# MSUT.net
KiCad netlist of a schematic drawn in EAGLE
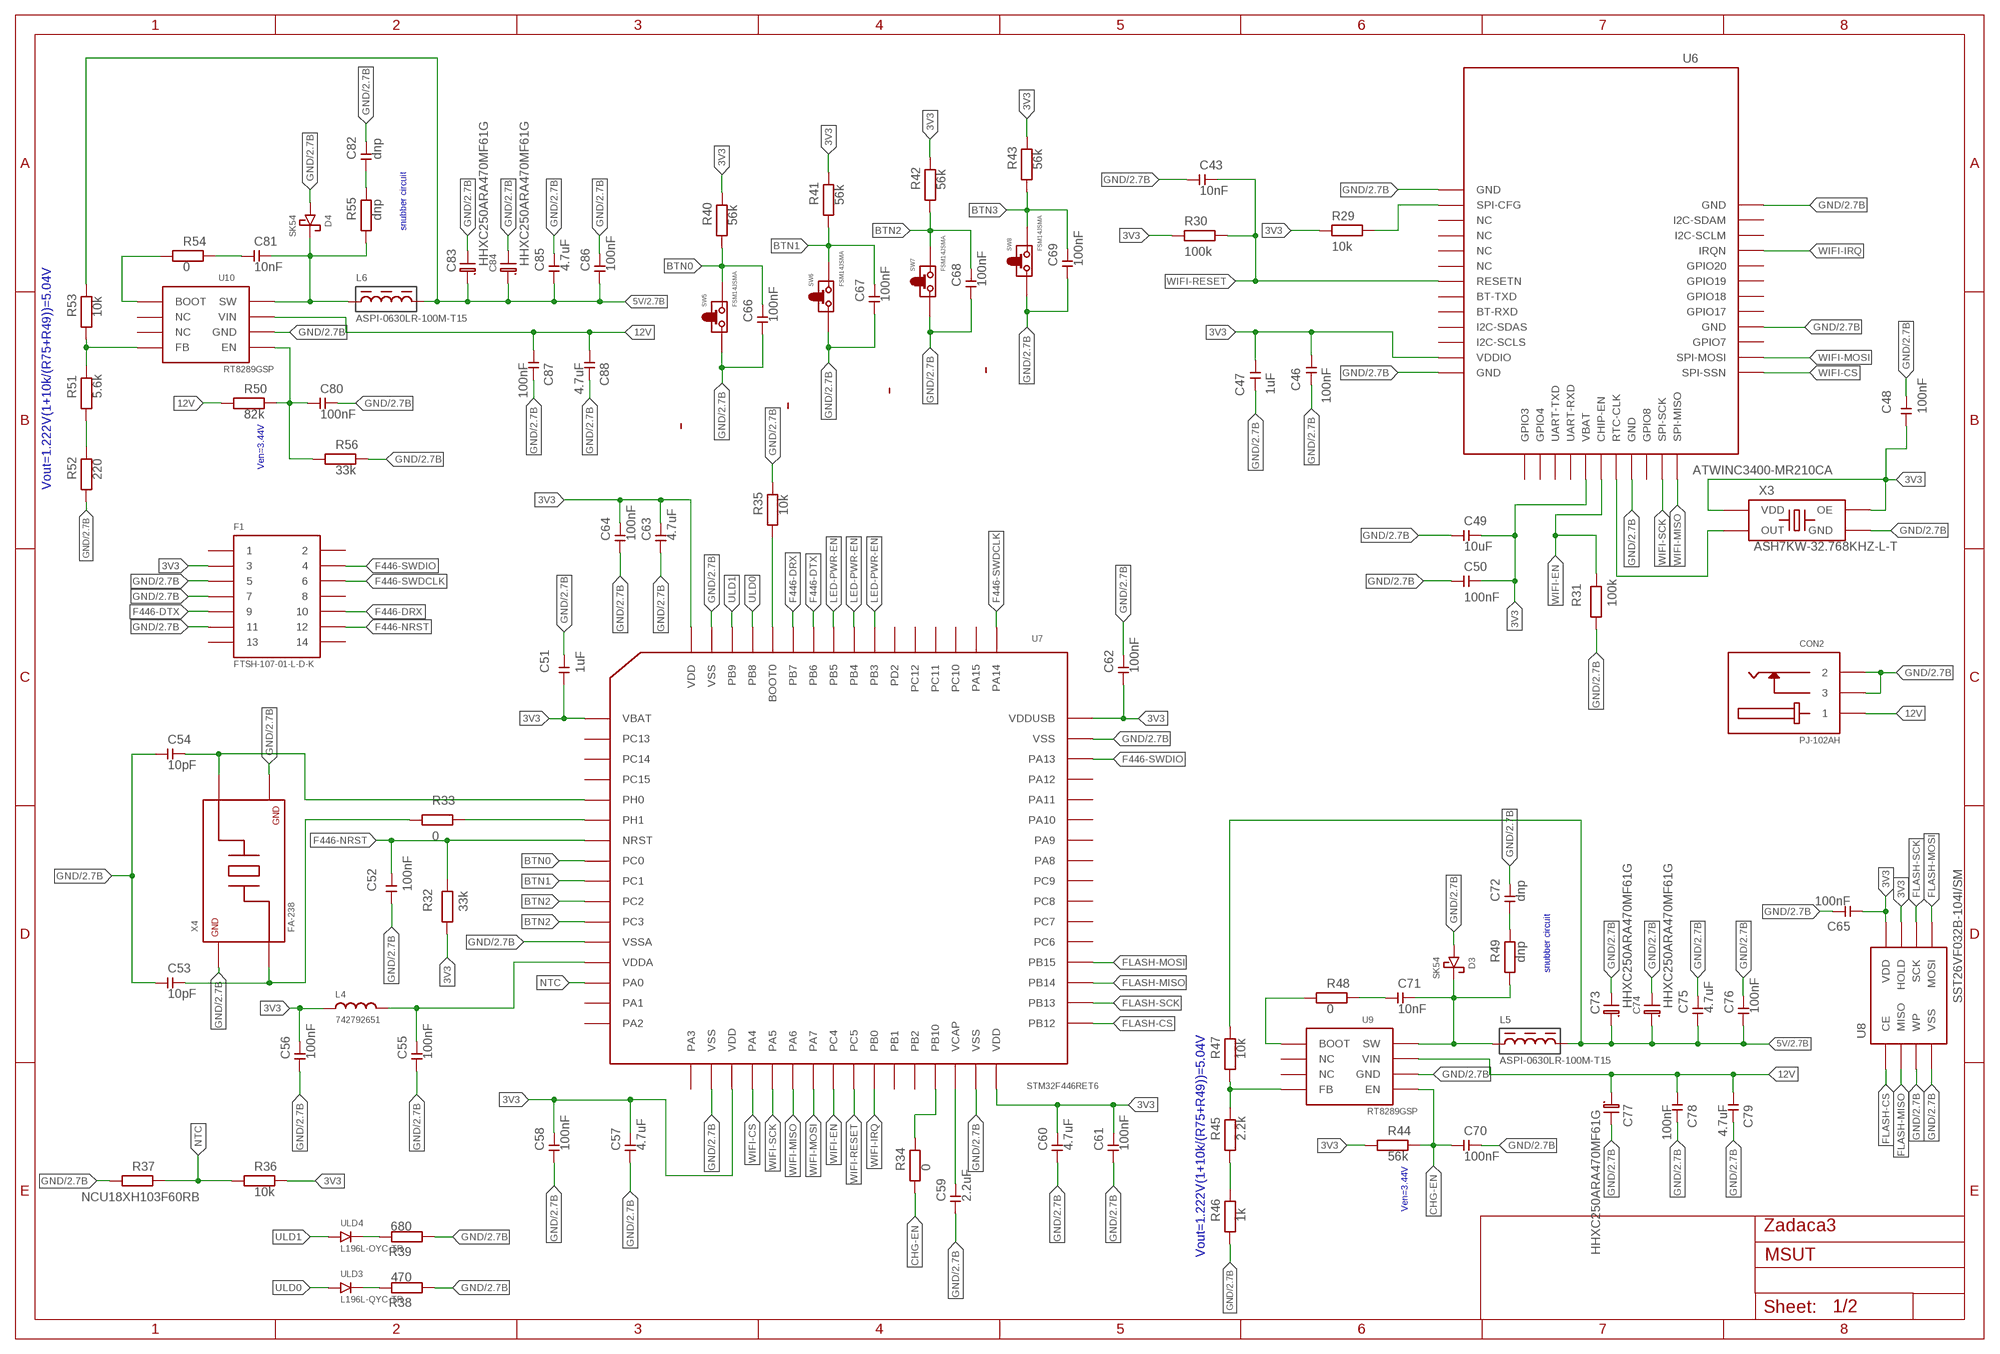
[diagram p0: schematic, sheet 1]
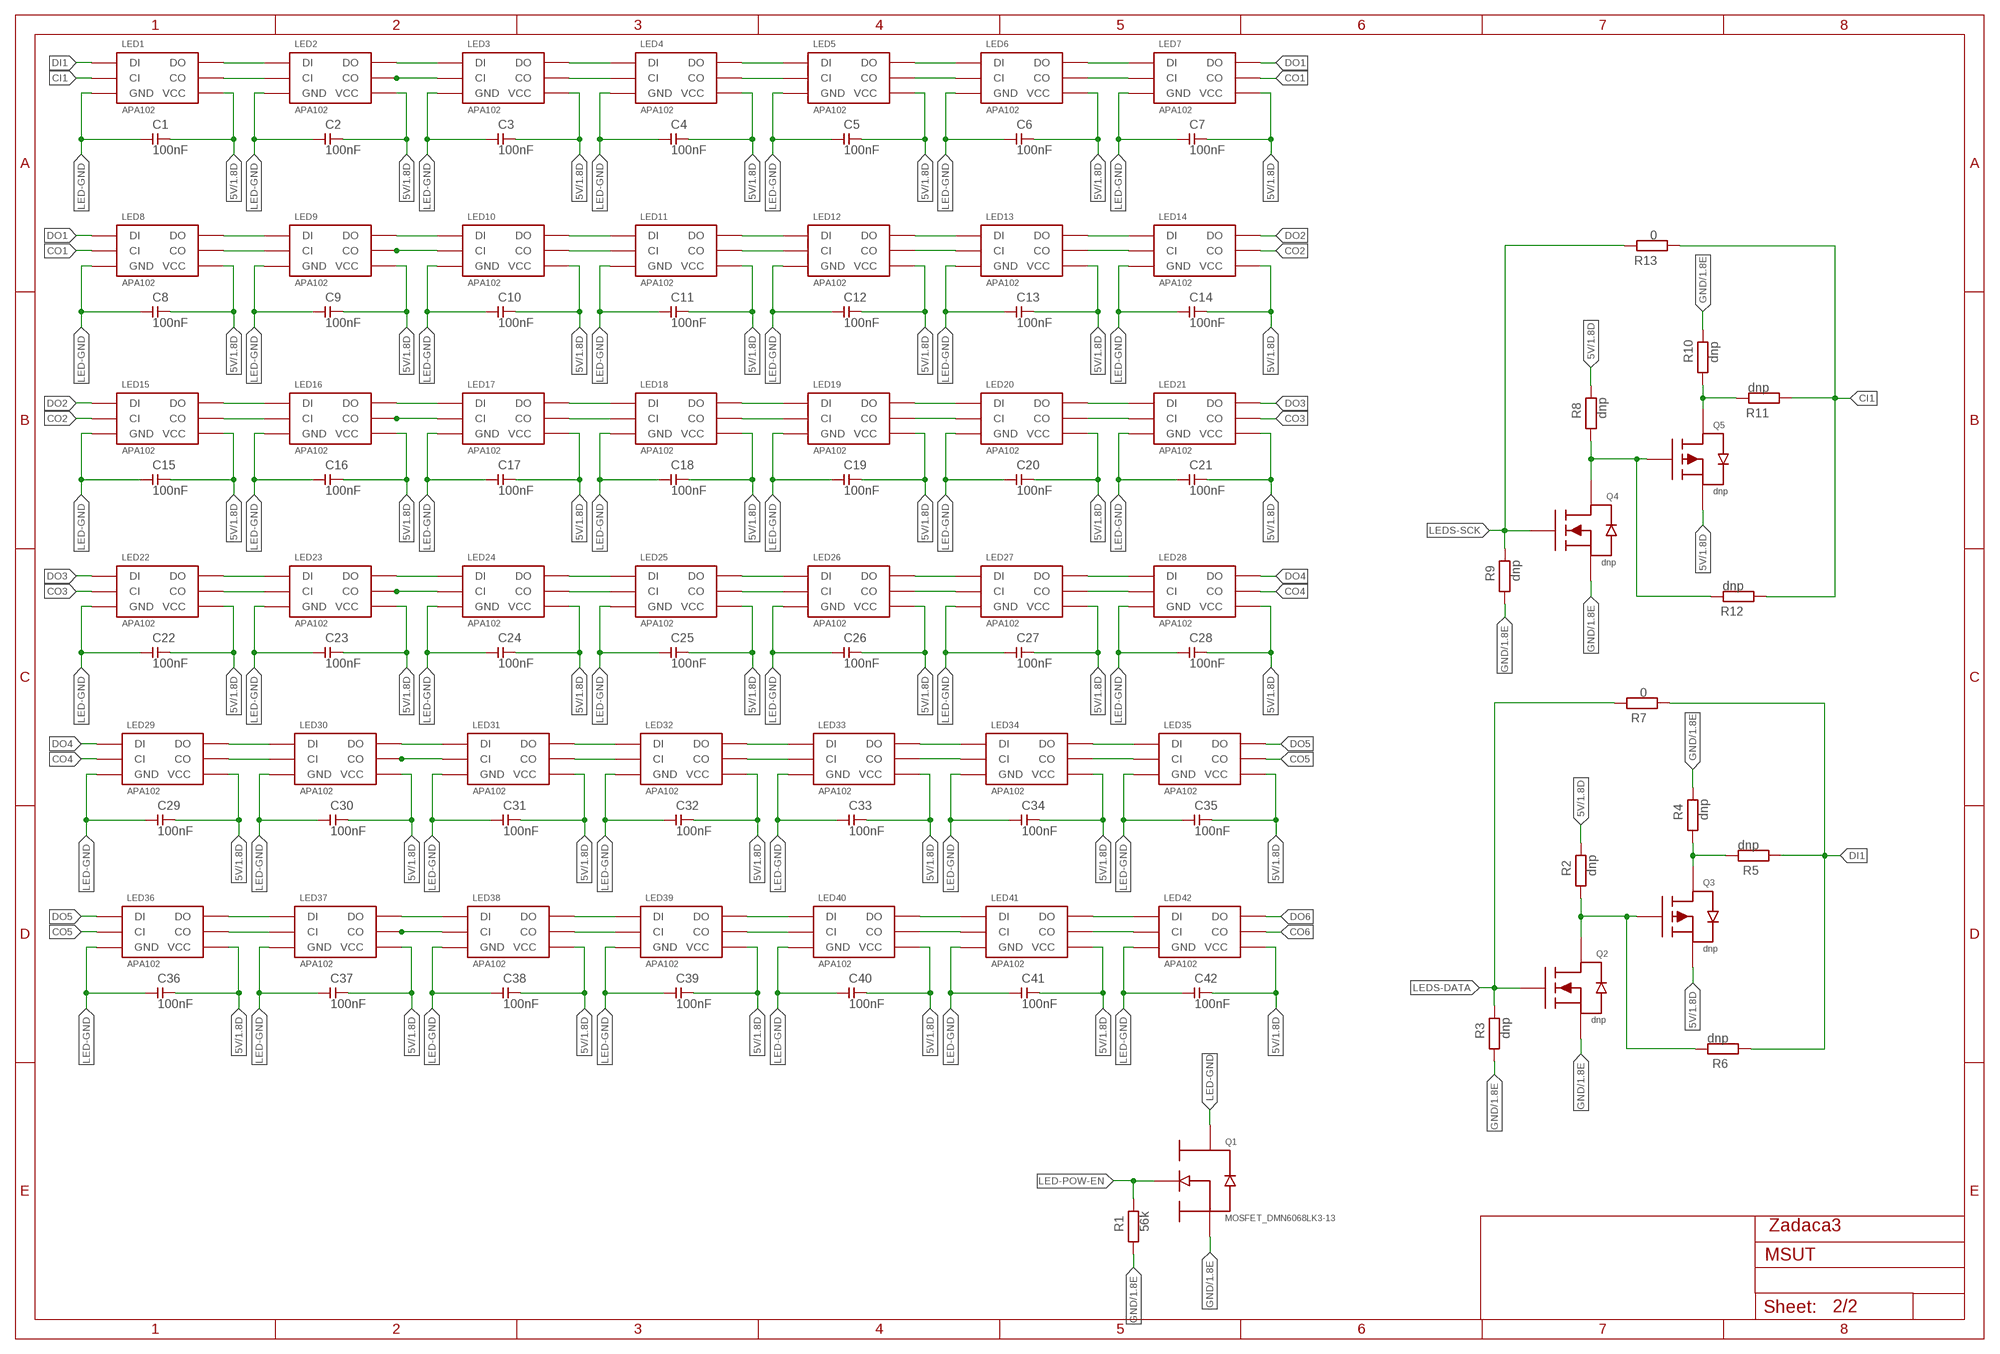
[diagram p1: schematic, sheet 2]

(export (version "E")
  (design (tool "Eeschema 10.0.6"))
  (components
    (comp (ref "C1")
      (value "100nF")
      (footprint "eagle-import:PACKAGE_0805")
      (libsource (lib "eagle-import") (part "CAPACITORB"))
    )
    (comp (ref "C2")
      (value "100nF")
      (footprint "eagle-import:PACKAGE_0805")
      (libsource (lib "eagle-import") (part "CAPACITORB"))
    )
    (comp (ref "C3")
      (value "100nF")
      (footprint "eagle-import:PACKAGE_0805")
      (libsource (lib "eagle-import") (part "CAPACITORB"))
    )
    (comp (ref "C4")
      (value "100nF")
      (footprint "eagle-import:PACKAGE_0805")
      (libsource (lib "eagle-import") (part "CAPACITORB"))
    )
    (comp (ref "C5")
      (value "100nF")
      (footprint "eagle-import:PACKAGE_0805")
      (libsource (lib "eagle-import") (part "CAPACITORB"))
    )
    (comp (ref "C6")
      (value "100nF")
      (footprint "eagle-import:PACKAGE_0805")
      (libsource (lib "eagle-import") (part "CAPACITORB"))
    )
    (comp (ref "C7")
      (value "100nF")
      (footprint "eagle-import:PACKAGE_0805")
      (libsource (lib "eagle-import") (part "CAPACITORB"))
    )
    (comp (ref "C8")
      (value "100nF")
      (footprint "eagle-import:PACKAGE_0805")
      (libsource (lib "eagle-import") (part "CAPACITORB"))
    )
    (comp (ref "C9")
      (value "100nF")
      (footprint "eagle-import:PACKAGE_0805")
      (libsource (lib "eagle-import") (part "CAPACITORB"))
    )
    (comp (ref "C10")
      (value "100nF")
      (footprint "eagle-import:PACKAGE_0805")
      (libsource (lib "eagle-import") (part "CAPACITORB"))
    )
    (comp (ref "C11")
      (value "100nF")
      (footprint "eagle-import:PACKAGE_0805")
      (libsource (lib "eagle-import") (part "CAPACITORB"))
    )
    (comp (ref "C12")
      (value "100nF")
      (footprint "eagle-import:PACKAGE_0805")
      (libsource (lib "eagle-import") (part "CAPACITORB"))
    )
    (comp (ref "C13")
      (value "100nF")
      (footprint "eagle-import:PACKAGE_0805")
      (libsource (lib "eagle-import") (part "CAPACITORB"))
    )
    (comp (ref "C14")
      (value "100nF")
      (footprint "eagle-import:PACKAGE_0805")
      (libsource (lib "eagle-import") (part "CAPACITORB"))
    )
    (comp (ref "C15")
      (value "100nF")
      (footprint "eagle-import:PACKAGE_0805")
      (libsource (lib "eagle-import") (part "CAPACITORB"))
    )
    (comp (ref "C16")
      (value "100nF")
      (footprint "eagle-import:PACKAGE_0805")
      (libsource (lib "eagle-import") (part "CAPACITORB"))
    )
    (comp (ref "C17")
      (value "100nF")
      (footprint "eagle-import:PACKAGE_0805")
      (libsource (lib "eagle-import") (part "CAPACITORB"))
    )
    (comp (ref "C18")
      (value "100nF")
      (footprint "eagle-import:PACKAGE_0805")
      (libsource (lib "eagle-import") (part "CAPACITORB"))
    )
    (comp (ref "C19")
      (value "100nF")
      (footprint "eagle-import:PACKAGE_0805")
      (libsource (lib "eagle-import") (part "CAPACITORB"))
    )
    (comp (ref "C20")
      (value "100nF")
      (footprint "eagle-import:PACKAGE_0805")
      (libsource (lib "eagle-import") (part "CAPACITORB"))
    )
    (comp (ref "C21")
      (value "100nF")
      (footprint "eagle-import:PACKAGE_0805")
      (libsource (lib "eagle-import") (part "CAPACITORB"))
    )
    (comp (ref "C22")
      (value "100nF")
      (footprint "eagle-import:PACKAGE_0805")
      (libsource (lib "eagle-import") (part "CAPACITORB"))
    )
    (comp (ref "C23")
      (value "100nF")
      (footprint "eagle-import:PACKAGE_0805")
      (libsource (lib "eagle-import") (part "CAPACITORB"))
    )
    (comp (ref "C24")
      (value "100nF")
      (footprint "eagle-import:PACKAGE_0805")
      (libsource (lib "eagle-import") (part "CAPACITORB"))
    )
    (comp (ref "C25")
      (value "100nF")
      (footprint "eagle-import:PACKAGE_0805")
      (libsource (lib "eagle-import") (part "CAPACITORB"))
    )
    (comp (ref "C26")
      (value "100nF")
      (footprint "eagle-import:PACKAGE_0805")
      (libsource (lib "eagle-import") (part "CAPACITORB"))
    )
    (comp (ref "C27")
      (value "100nF")
      (footprint "eagle-import:PACKAGE_0805")
      (libsource (lib "eagle-import") (part "CAPACITORB"))
    )
    (comp (ref "C28")
      (value "100nF")
      (footprint "eagle-import:PACKAGE_0805")
      (libsource (lib "eagle-import") (part "CAPACITORB"))
    )
    (comp (ref "C29")
      (value "100nF")
      (footprint "eagle-import:PACKAGE_0805")
      (libsource (lib "eagle-import") (part "CAPACITORB"))
    )
    (comp (ref "C30")
      (value "100nF")
      (footprint "eagle-import:PACKAGE_0805")
      (libsource (lib "eagle-import") (part "CAPACITORB"))
    )
    (comp (ref "C31")
      (value "100nF")
      (footprint "eagle-import:PACKAGE_0805")
      (libsource (lib "eagle-import") (part "CAPACITORB"))
    )
    (comp (ref "C32")
      (value "100nF")
      (footprint "eagle-import:PACKAGE_0805")
      (libsource (lib "eagle-import") (part "CAPACITORB"))
    )
    (comp (ref "C33")
      (value "100nF")
      (footprint "eagle-import:PACKAGE_0805")
      (libsource (lib "eagle-import") (part "CAPACITORB"))
    )
    (comp (ref "C34")
      (value "100nF")
      (footprint "eagle-import:PACKAGE_0805")
      (libsource (lib "eagle-import") (part "CAPACITORB"))
    )
    (comp (ref "C35")
      (value "100nF")
      (footprint "eagle-import:PACKAGE_0805")
      (libsource (lib "eagle-import") (part "CAPACITORB"))
    )
    (comp (ref "C36")
      (value "100nF")
      (footprint "eagle-import:PACKAGE_0805")
      (libsource (lib "eagle-import") (part "CAPACITORB"))
    )
    (comp (ref "C37")
      (value "100nF")
      (footprint "eagle-import:PACKAGE_0805")
      (libsource (lib "eagle-import") (part "CAPACITORB"))
    )
    (comp (ref "C38")
      (value "100nF")
      (footprint "eagle-import:PACKAGE_0805")
      (libsource (lib "eagle-import") (part "CAPACITORB"))
    )
    (comp (ref "C39")
      (value "100nF")
      (footprint "eagle-import:PACKAGE_0805")
      (libsource (lib "eagle-import") (part "CAPACITORB"))
    )
    (comp (ref "C40")
      (value "100nF")
      (footprint "eagle-import:PACKAGE_0805")
      (libsource (lib "eagle-import") (part "CAPACITORB"))
    )
    (comp (ref "C41")
      (value "100nF")
      (footprint "eagle-import:PACKAGE_0805")
      (libsource (lib "eagle-import") (part "CAPACITORB"))
    )
    (comp (ref "C42")
      (value "100nF")
      (footprint "eagle-import:PACKAGE_0805")
      (libsource (lib "eagle-import") (part "CAPACITORB"))
    )
    (comp (ref "LED1")
      (value "RGB_LED")
      (footprint "eagle-import:TAPE&REEL_LED")
      (libsource (lib "eagle-import") (part "RGB_LED"))
    )
    (comp (ref "LED2")
      (value "RGB_LED")
      (footprint "eagle-import:TAPE&REEL_LED")
      (libsource (lib "eagle-import") (part "RGB_LED"))
    )
    (comp (ref "LED3")
      (value "RGB_LED")
      (footprint "eagle-import:TAPE&REEL_LED")
      (libsource (lib "eagle-import") (part "RGB_LED"))
    )
    (comp (ref "LED4")
      (value "RGB_LED")
      (footprint "eagle-import:TAPE&REEL_LED")
      (libsource (lib "eagle-import") (part "RGB_LED"))
    )
    (comp (ref "LED5")
      (value "RGB_LED")
      (footprint "eagle-import:TAPE&REEL_LED")
      (libsource (lib "eagle-import") (part "RGB_LED"))
    )
    (comp (ref "LED6")
      (value "RGB_LED")
      (footprint "eagle-import:TAPE&REEL_LED")
      (libsource (lib "eagle-import") (part "RGB_LED"))
    )
    (comp (ref "LED7")
      (value "RGB_LED")
      (footprint "eagle-import:TAPE&REEL_LED")
      (libsource (lib "eagle-import") (part "RGB_LED"))
    )
    (comp (ref "LED8")
      (value "RGB_LED")
      (footprint "eagle-import:TAPE&REEL_LED")
      (libsource (lib "eagle-import") (part "RGB_LED"))
    )
    (comp (ref "LED9")
      (value "RGB_LED")
      (footprint "eagle-import:TAPE&REEL_LED")
      (libsource (lib "eagle-import") (part "RGB_LED"))
    )
    (comp (ref "LED10")
      (value "RGB_LED")
      (footprint "eagle-import:TAPE&REEL_LED")
      (libsource (lib "eagle-import") (part "RGB_LED"))
    )
    (comp (ref "LED11")
      (value "RGB_LED")
      (footprint "eagle-import:TAPE&REEL_LED")
      (libsource (lib "eagle-import") (part "RGB_LED"))
    )
    (comp (ref "LED12")
      (value "RGB_LED")
      (footprint "eagle-import:TAPE&REEL_LED")
      (libsource (lib "eagle-import") (part "RGB_LED"))
    )
    (comp (ref "LED13")
      (value "RGB_LED")
      (footprint "eagle-import:TAPE&REEL_LED")
      (libsource (lib "eagle-import") (part "RGB_LED"))
    )
    (comp (ref "LED14")
      (value "RGB_LED")
      (footprint "eagle-import:TAPE&REEL_LED")
      (libsource (lib "eagle-import") (part "RGB_LED"))
    )
    (comp (ref "LED15")
      (value "RGB_LED")
      (footprint "eagle-import:TAPE&REEL_LED")
      (libsource (lib "eagle-import") (part "RGB_LED"))
    )
    (comp (ref "LED16")
      (value "RGB_LED")
      (footprint "eagle-import:TAPE&REEL_LED")
      (libsource (lib "eagle-import") (part "RGB_LED"))
    )
    (comp (ref "LED17")
      (value "RGB_LED")
      (footprint "eagle-import:TAPE&REEL_LED")
      (libsource (lib "eagle-import") (part "RGB_LED"))
    )
    (comp (ref "LED18")
      (value "RGB_LED")
      (footprint "eagle-import:TAPE&REEL_LED")
      (libsource (lib "eagle-import") (part "RGB_LED"))
    )
    (comp (ref "LED19")
      (value "RGB_LED")
      (footprint "eagle-import:TAPE&REEL_LED")
      (libsource (lib "eagle-import") (part "RGB_LED"))
    )
    (comp (ref "LED20")
      (value "RGB_LED")
      (footprint "eagle-import:TAPE&REEL_LED")
      (libsource (lib "eagle-import") (part "RGB_LED"))
    )
    (comp (ref "LED21")
      (value "RGB_LED")
      (footprint "eagle-import:TAPE&REEL_LED")
      (libsource (lib "eagle-import") (part "RGB_LED"))
    )
    (comp (ref "LED22")
      (value "RGB_LED")
      (footprint "eagle-import:TAPE&REEL_LED")
      (libsource (lib "eagle-import") (part "RGB_LED"))
    )
    (comp (ref "LED23")
      (value "RGB_LED")
      (footprint "eagle-import:TAPE&REEL_LED")
      (libsource (lib "eagle-import") (part "RGB_LED"))
    )
    (comp (ref "LED24")
      (value "RGB_LED")
      (footprint "eagle-import:TAPE&REEL_LED")
      (libsource (lib "eagle-import") (part "RGB_LED"))
    )
    (comp (ref "LED25")
      (value "RGB_LED")
      (footprint "eagle-import:TAPE&REEL_LED")
      (libsource (lib "eagle-import") (part "RGB_LED"))
    )
    (comp (ref "LED26")
      (value "RGB_LED")
      (footprint "eagle-import:TAPE&REEL_LED")
      (libsource (lib "eagle-import") (part "RGB_LED"))
    )
    (comp (ref "LED27")
      (value "RGB_LED")
      (footprint "eagle-import:TAPE&REEL_LED")
      (libsource (lib "eagle-import") (part "RGB_LED"))
    )
    (comp (ref "LED28")
      (value "RGB_LED")
      (footprint "eagle-import:TAPE&REEL_LED")
      (libsource (lib "eagle-import") (part "RGB_LED"))
    )
    (comp (ref "LED29")
      (value "RGB_LED")
      (footprint "eagle-import:TAPE&REEL_LED")
      (libsource (lib "eagle-import") (part "RGB_LED"))
    )
    (comp (ref "LED30")
      (value "RGB_LED")
      (footprint "eagle-import:TAPE&REEL_LED")
      (libsource (lib "eagle-import") (part "RGB_LED"))
    )
    (comp (ref "LED31")
      (value "RGB_LED")
      (footprint "eagle-import:TAPE&REEL_LED")
      (libsource (lib "eagle-import") (part "RGB_LED"))
    )
    (comp (ref "LED32")
      (value "RGB_LED")
      (footprint "eagle-import:TAPE&REEL_LED")
      (libsource (lib "eagle-import") (part "RGB_LED"))
    )
    (comp (ref "LED33")
      (value "RGB_LED")
      (footprint "eagle-import:TAPE&REEL_LED")
      (libsource (lib "eagle-import") (part "RGB_LED"))
    )
    (comp (ref "LED34")
      (value "RGB_LED")
      (footprint "eagle-import:TAPE&REEL_LED")
      (libsource (lib "eagle-import") (part "RGB_LED"))
    )
    (comp (ref "LED35")
      (value "RGB_LED")
      (footprint "eagle-import:TAPE&REEL_LED")
      (libsource (lib "eagle-import") (part "RGB_LED"))
    )
    (comp (ref "LED36")
      (value "RGB_LED")
      (footprint "eagle-import:TAPE&REEL_LED")
      (libsource (lib "eagle-import") (part "RGB_LED"))
    )
    (comp (ref "LED37")
      (value "RGB_LED")
      (footprint "eagle-import:TAPE&REEL_LED")
      (libsource (lib "eagle-import") (part "RGB_LED"))
    )
    (comp (ref "LED38")
      (value "RGB_LED")
      (footprint "eagle-import:TAPE&REEL_LED")
      (libsource (lib "eagle-import") (part "RGB_LED"))
    )
    (comp (ref "LED39")
      (value "RGB_LED")
      (footprint "eagle-import:TAPE&REEL_LED")
      (libsource (lib "eagle-import") (part "RGB_LED"))
    )
    (comp (ref "LED40")
      (value "RGB_LED")
      (footprint "eagle-import:TAPE&REEL_LED")
      (libsource (lib "eagle-import") (part "RGB_LED"))
    )
    (comp (ref "LED41")
      (value "RGB_LED")
      (footprint "eagle-import:TAPE&REEL_LED")
      (libsource (lib "eagle-import") (part "RGB_LED"))
    )
    (comp (ref "LED42")
      (value "RGB_LED")
      (footprint "eagle-import:TAPE&REEL_LED")
      (libsource (lib "eagle-import") (part "RGB_LED"))
    )
    (comp (ref "Q1")
      (value "MOSFET_DMN6068LK3-13")
      (footprint "eagle-import:TO252-3L")
      (libsource (lib "eagle-import") (part "MOSFET_DMN6068LK3-13"))
    )
    (comp (ref "Q2")
      (value "NCHANNEL_MOSFET")
      (footprint "eagle-import:SOT-23-3")
      (libsource (lib "eagle-import") (part "NCHANNEL_MOSFET"))
    )
    (comp (ref "Q3")
      (value "PCHANNEL_MOSFET")
      (footprint "eagle-import:SOT-23-3")
      (libsource (lib "eagle-import") (part "PCHANNEL_MOSFET"))
    )
    (comp (ref "Q4")
      (value "NCHANNEL_MOSFET")
      (footprint "eagle-import:SOT-23-3")
      (libsource (lib "eagle-import") (part "NCHANNEL_MOSFET"))
    )
    (comp (ref "Q5")
      (value "PCHANNEL_MOSFET")
      (footprint "eagle-import:SOT-23-3")
      (libsource (lib "eagle-import") (part "PCHANNEL_MOSFET"))
    )
    (comp (ref "R1")
      (value "56k")
      (footprint "eagle-import:PACKAGE_0805")
      (libsource (lib "eagle-import") (part "RESISTOR"))
    )
    (comp (ref "R2")
      (value "dnp")
      (footprint "eagle-import:PACKAGE_0805")
      (libsource (lib "eagle-import") (part "RESISTOR"))
    )
    (comp (ref "R3")
      (value "dnp")
      (footprint "eagle-import:PACKAGE_0805")
      (libsource (lib "eagle-import") (part "RESISTOR"))
    )
    (comp (ref "R4")
      (value "dnp")
      (footprint "eagle-import:PACKAGE_0805")
      (libsource (lib "eagle-import") (part "RESISTOR"))
    )
    (comp (ref "R5")
      (value "dnp")
      (footprint "eagle-import:PACKAGE_0805")
      (libsource (lib "eagle-import") (part "RESISTOR"))
    )
    (comp (ref "R6")
      (value "dnp")
      (footprint "eagle-import:PACKAGE_0805")
      (libsource (lib "eagle-import") (part "RESISTOR"))
    )
    (comp (ref "R7")
      (value "0")
      (footprint "eagle-import:PACKAGE_0805")
      (libsource (lib "eagle-import") (part "RESISTOR"))
    )
    (comp (ref "R8")
      (value "dnp")
      (footprint "eagle-import:PACKAGE_0805")
      (libsource (lib "eagle-import") (part "RESISTOR"))
    )
    (comp (ref "R9")
      (value "dnp")
      (footprint "eagle-import:PACKAGE_0805")
      (libsource (lib "eagle-import") (part "RESISTOR"))
    )
    (comp (ref "R10")
      (value "dnp")
      (footprint "eagle-import:PACKAGE_0805")
      (libsource (lib "eagle-import") (part "RESISTOR"))
    )
    (comp (ref "R11")
      (value "dnp")
      (footprint "eagle-import:PACKAGE_0805")
      (libsource (lib "eagle-import") (part "RESISTOR"))
    )
    (comp (ref "R12")
      (value "dnp")
      (footprint "eagle-import:PACKAGE_0805")
      (libsource (lib "eagle-import") (part "RESISTOR"))
    )
    (comp (ref "R13")
      (value "0")
      (footprint "eagle-import:PACKAGE_0805")
      (libsource (lib "eagle-import") (part "RESISTOR"))
    )
    (comp (ref "C43")
      (value "10nF")
      (footprint "eagle-import:PACKAGE_0805")
      (libsource (lib "eagle-import") (part "CAPACITORB"))
    )
    (comp (ref "C46")
      (value "100nF")
      (footprint "eagle-import:PACKAGE_0805")
      (libsource (lib "eagle-import") (part "CAPACITORB"))
    )
    (comp (ref "C47")
      (value "1uF")
      (footprint "eagle-import:PACKAGE_0805")
      (libsource (lib "eagle-import") (part "CAPACITORB"))
    )
    (comp (ref "C48")
      (value "100nF")
      (footprint "eagle-import:PACKAGE_0805")
      (libsource (lib "eagle-import") (part "CAPACITORB"))
    )
    (comp (ref "C49")
      (value "10uF")
      (footprint "eagle-import:PACKAGE_0805")
      (libsource (lib "eagle-import") (part "CAPACITORB"))
    )
    (comp (ref "C50")
      (value "100nF")
      (footprint "eagle-import:PACKAGE_0805")
      (libsource (lib "eagle-import") (part "CAPACITORB"))
    )
    (comp (ref "C51")
      (value "1uF")
      (footprint "eagle-import:PACKAGE_0805")
      (libsource (lib "eagle-import") (part "CAPACITORB"))
    )
    (comp (ref "C52")
      (value "100nF")
      (footprint "eagle-import:PACKAGE_0805")
      (libsource (lib "eagle-import") (part "CAPACITORB"))
    )
    (comp (ref "C53")
      (value "10pF")
      (footprint "eagle-import:PACKAGE_0805")
      (libsource (lib "eagle-import") (part "CAPACITORB"))
    )
    (comp (ref "C54")
      (value "10pF")
      (footprint "eagle-import:PACKAGE_0805")
      (libsource (lib "eagle-import") (part "CAPACITORB"))
    )
    (comp (ref "C55")
      (value "100nF")
      (footprint "eagle-import:PACKAGE_0805")
      (libsource (lib "eagle-import") (part "CAPACITORB"))
    )
    (comp (ref "C56")
      (value "100nF")
      (footprint "eagle-import:PACKAGE_0805")
      (libsource (lib "eagle-import") (part "CAPACITORB"))
    )
    (comp (ref "C57")
      (value "4.7uF")
      (footprint "eagle-import:PACKAGE_0805")
      (libsource (lib "eagle-import") (part "CAPACITORB"))
    )
    (comp (ref "C58")
      (value "100nF")
      (footprint "eagle-import:PACKAGE_0805")
      (libsource (lib "eagle-import") (part "CAPACITORB"))
    )
    (comp (ref "C59")
      (value "2.2uF")
      (footprint "eagle-import:PACKAGE_0805")
      (libsource (lib "eagle-import") (part "CAPACITORB"))
    )
    (comp (ref "C60")
      (value "4.7uF")
      (footprint "eagle-import:PACKAGE_0805")
      (libsource (lib "eagle-import") (part "CAPACITORB"))
    )
    (comp (ref "C61")
      (value "100nF")
      (footprint "eagle-import:PACKAGE_0805")
      (libsource (lib "eagle-import") (part "CAPACITORB"))
    )
    (comp (ref "C62")
      (value "100nF")
      (footprint "eagle-import:PACKAGE_0805")
      (libsource (lib "eagle-import") (part "CAPACITORB"))
    )
    (comp (ref "C63")
      (value "4.7uF")
      (footprint "eagle-import:PACKAGE_0805")
      (libsource (lib "eagle-import") (part "CAPACITORB"))
    )
    (comp (ref "C64")
      (value "100nF")
      (footprint "eagle-import:PACKAGE_0805")
      (libsource (lib "eagle-import") (part "CAPACITORB"))
    )
    (comp (ref "C65")
      (value "100nF")
      (footprint "eagle-import:PACKAGE_0805")
      (libsource (lib "eagle-import") (part "CAPACITORB"))
    )
    (comp (ref "C66")
      (value "100nF")
      (footprint "eagle-import:PACKAGE_0805")
      (libsource (lib "eagle-import") (part "CAPACITORB"))
    )
    (comp (ref "C67")
      (value "100nF")
      (footprint "eagle-import:PACKAGE_0805")
      (libsource (lib "eagle-import") (part "CAPACITORB"))
    )
    (comp (ref "C68")
      (value "100nF")
      (footprint "eagle-import:PACKAGE_0805")
      (libsource (lib "eagle-import") (part "CAPACITORB"))
    )
    (comp (ref "C69")
      (value "100nF")
      (footprint "eagle-import:PACKAGE_0805")
      (libsource (lib "eagle-import") (part "CAPACITORB"))
    )
    (comp (ref "C70")
      (value "100nF")
      (footprint "eagle-import:PACKAGE_0805")
      (libsource (lib "eagle-import") (part "CAPACITORB"))
    )
    (comp (ref "C71")
      (value "10nF")
      (footprint "eagle-import:PACKAGE_0805")
      (libsource (lib "eagle-import") (part "CAPACITORB"))
    )
    (comp (ref "C72")
      (value "dnp")
      (footprint "eagle-import:PACKAGE_0805")
      (libsource (lib "eagle-import") (part "CAPACITORB"))
    )
    (comp (ref "C73")
      (value "HHXC250ARA470MF61G")
      (footprint "eagle-import:PACKAGE_EL_CAP_HXC")
      (libsource (lib "eagle-import") (part "ELECTROLIC_CAPACTIOR"))
    )
    (comp (ref "C74")
      (value "HHXC250ARA470MF61G")
      (footprint "eagle-import:PACKAGE_EL_CAP_HXC")
      (libsource (lib "eagle-import") (part "ELECTROLIC_CAPACTIOR"))
    )
    (comp (ref "C75")
      (value "4.7uF")
      (footprint "eagle-import:PACKAGE_0805")
      (libsource (lib "eagle-import") (part "CAPACITORB"))
    )
    (comp (ref "C76")
      (value "100nF")
      (footprint "eagle-import:PACKAGE_0805")
      (libsource (lib "eagle-import") (part "CAPACITORB"))
    )
    (comp (ref "C77")
      (value "HHXB350ARA470MF61G")
      (footprint "eagle-import:PACKAGE_EL_CAP_HXC")
      (libsource (lib "eagle-import") (part "ELECTROLIC_CAPACTIOR"))
    )
    (comp (ref "C78")
      (value "100nF")
      (footprint "eagle-import:PACKAGE_0805")
      (libsource (lib "eagle-import") (part "CAPACITORB"))
    )
    (comp (ref "C79")
      (value "4.7uF")
      (footprint "eagle-import:PACKAGE_0805")
      (libsource (lib "eagle-import") (part "CAPACITORB"))
    )
    (comp (ref "C80")
      (value "100nF")
      (footprint "eagle-import:PACKAGE_0805")
      (libsource (lib "eagle-import") (part "CAPACITORB"))
    )
    (comp (ref "C81")
      (value "10nF")
      (footprint "eagle-import:PACKAGE_0805")
      (libsource (lib "eagle-import") (part "CAPACITORB"))
    )
    (comp (ref "C82")
      (value "dnp")
      (footprint "eagle-import:PACKAGE_0805")
      (libsource (lib "eagle-import") (part "CAPACITORB"))
    )
    (comp (ref "C83")
      (value "HHXC250ARA470MF61G")
      (footprint "eagle-import:PACKAGE_EL_CAP_HXC")
      (libsource (lib "eagle-import") (part "ELECTROLIC_CAPACTIOR"))
    )
    (comp (ref "C84")
      (value "HHXC250ARA470MF61G")
      (footprint "eagle-import:PACKAGE_EL_CAP_HXC")
      (libsource (lib "eagle-import") (part "ELECTROLIC_CAPACTIOR"))
    )
    (comp (ref "C85")
      (value "4.7uF")
      (footprint "eagle-import:PACKAGE_0805")
      (libsource (lib "eagle-import") (part "CAPACITORB"))
    )
    (comp (ref "C86")
      (value "100nF")
      (footprint "eagle-import:PACKAGE_0805")
      (libsource (lib "eagle-import") (part "CAPACITORB"))
    )
    (comp (ref "C87")
      (value "100nF")
      (footprint "eagle-import:PACKAGE_0805")
      (libsource (lib "eagle-import") (part "CAPACITORB"))
    )
    (comp (ref "C88")
      (value "4.7uF")
      (footprint "eagle-import:PACKAGE_0805")
      (libsource (lib "eagle-import") (part "CAPACITORB"))
    )
    (comp (ref "CON2")
      (value "PJ-102AH")
      (footprint "eagle-import:TRAY_PJ-102AH")
      (libsource (lib "eagle-import") (part "PJ-102AH_CONNECTOR"))
    )
    (comp (ref "D3")
      (value "SK54")
      (footprint "eagle-import:D0-214AB")
      (libsource (lib "eagle-import") (part "SHOTTKY_DIODE"))
    )
    (comp (ref "D4")
      (value "SK54")
      (footprint "eagle-import:D0-214AB")
      (libsource (lib "eagle-import") (part "SHOTTKY_DIODE"))
    )
    (comp (ref "F1")
      (value "FTSH-107-01-L-D-K")
      (footprint "eagle-import:TUBE_FTSH-107-01-L-D-K")
      (libsource (lib "eagle-import") (part "FTSH-107-01-L-D-K"))
    )
    (comp (ref "L4")
      (value "742792651")
      (footprint "eagle-import:PACKAGE_0805")
      (libsource (lib "eagle-import") (part "INDUCTOR"))
    )
    (comp (ref "L5")
      (value "ASPI-0630LR-100M-T15")
      (footprint "eagle-import:PACKAGE_ASPI-0630")
      (libsource (lib "eagle-import") (part "ASPI-0630LR-100M-T15"))
    )
    (comp (ref "L6")
      (value "ASPI-0630LR-100M-T15")
      (footprint "eagle-import:PACKAGE_ASPI-0630")
      (libsource (lib "eagle-import") (part "ASPI-0630LR-100M-T15"))
    )
    (comp (ref "R29")
      (value "10k")
      (footprint "eagle-import:PACKAGE_0805")
      (libsource (lib "eagle-import") (part "RESISTOR"))
    )
    (comp (ref "R30")
      (value "100k")
      (footprint "eagle-import:PACKAGE_0805")
      (libsource (lib "eagle-import") (part "RESISTOR"))
    )
    (comp (ref "R31")
      (value "100k")
      (footprint "eagle-import:PACKAGE_0805")
      (libsource (lib "eagle-import") (part "RESISTOR"))
    )
    (comp (ref "R32")
      (value "33k")
      (footprint "eagle-import:PACKAGE_0805")
      (libsource (lib "eagle-import") (part "RESISTOR"))
    )
    (comp (ref "R33")
      (value "0")
      (footprint "eagle-import:PACKAGE_0805")
      (libsource (lib "eagle-import") (part "RESISTOR"))
    )
    (comp (ref "R34")
      (value "0")
      (footprint "eagle-import:PACKAGE_0805")
      (libsource (lib "eagle-import") (part "RESISTOR"))
    )
    (comp (ref "R35")
      (value "10k")
      (footprint "eagle-import:PACKAGE_0805")
      (libsource (lib "eagle-import") (part "RESISTOR"))
    )
    (comp (ref "R36")
      (value "10k")
      (footprint "eagle-import:PACKAGE_0805")
      (libsource (lib "eagle-import") (part "RESISTOR"))
    )
    (comp (ref "R37")
      (value "NCU18XH103F60RB")
      (footprint "eagle-import:PACKAGE_0805")
      (libsource (lib "eagle-import") (part "RESISTOR"))
    )
    (comp (ref "R38")
      (value "470")
      (footprint "eagle-import:PACKAGE_0805")
      (libsource (lib "eagle-import") (part "RESISTOR"))
    )
    (comp (ref "R39")
      (value "680")
      (footprint "eagle-import:PACKAGE_0805")
      (libsource (lib "eagle-import") (part "RESISTOR"))
    )
    (comp (ref "R40")
      (value "56k")
      (footprint "eagle-import:PACKAGE_0805")
      (libsource (lib "eagle-import") (part "RESISTOR"))
    )
    (comp (ref "R41")
      (value "56k")
      (footprint "eagle-import:PACKAGE_0805")
      (libsource (lib "eagle-import") (part "RESISTOR"))
    )
    (comp (ref "R42")
      (value "56k")
      (footprint "eagle-import:PACKAGE_0805")
      (libsource (lib "eagle-import") (part "RESISTOR"))
    )
    (comp (ref "R43")
      (value "56k")
      (footprint "eagle-import:PACKAGE_0805")
      (libsource (lib "eagle-import") (part "RESISTOR"))
    )
    (comp (ref "R44")
      (value "56k")
      (footprint "eagle-import:PACKAGE_0805")
      (libsource (lib "eagle-import") (part "RESISTOR"))
    )
    (comp (ref "R45")
      (value "2.2k")
      (footprint "eagle-import:PACKAGE_0805")
      (libsource (lib "eagle-import") (part "RESISTOR"))
    )
    (comp (ref "R46")
      (value "1k")
      (footprint "eagle-import:PACKAGE_0805")
      (libsource (lib "eagle-import") (part "RESISTOR"))
    )
    (comp (ref "R47")
      (value "10k")
      (footprint "eagle-import:PACKAGE_0805")
      (libsource (lib "eagle-import") (part "RESISTOR"))
    )
    (comp (ref "R48")
      (value "0")
      (footprint "eagle-import:PACKAGE_0805")
      (libsource (lib "eagle-import") (part "RESISTOR"))
    )
    (comp (ref "R49")
      (value "dnp")
      (footprint "eagle-import:PACKAGE_0805")
      (libsource (lib "eagle-import") (part "RESISTOR"))
    )
    (comp (ref "R50")
      (value "82k")
      (footprint "eagle-import:PACKAGE_0805")
      (libsource (lib "eagle-import") (part "RESISTOR"))
    )
    (comp (ref "R51")
      (value "5.6k")
      (footprint "eagle-import:PACKAGE_0805")
      (libsource (lib "eagle-import") (part "RESISTOR"))
    )
    (comp (ref "R52")
      (value "220")
      (footprint "eagle-import:PACKAGE_0805")
      (libsource (lib "eagle-import") (part "RESISTOR"))
    )
    (comp (ref "R53")
      (value "10k")
      (footprint "eagle-import:PACKAGE_0805")
      (libsource (lib "eagle-import") (part "RESISTOR"))
    )
    (comp (ref "R54")
      (value "0")
      (footprint "eagle-import:PACKAGE_0805")
      (libsource (lib "eagle-import") (part "RESISTOR"))
    )
    (comp (ref "R55")
      (value "dnp")
      (footprint "eagle-import:PACKAGE_0805")
      (libsource (lib "eagle-import") (part "RESISTOR"))
    )
    (comp (ref "R56")
      (value "33k")
      (footprint "eagle-import:PACKAGE_0805")
      (libsource (lib "eagle-import") (part "RESISTOR"))
    )
    (comp (ref "SW5")
      (value "FSM14JSMA")
      (footprint "eagle-import:FSM14JSMA")
      (libsource (lib "eagle-import") (part "PUSHBUTTON"))
    )
    (comp (ref "SW6")
      (value "FSM14JSMA")
      (footprint "eagle-import:FSM14JSMA")
      (libsource (lib "eagle-import") (part "PUSHBUTTON"))
    )
    (comp (ref "SW7")
      (value "FSM14JSMA")
      (footprint "eagle-import:FSM14JSMA")
      (libsource (lib "eagle-import") (part "PUSHBUTTON"))
    )
    (comp (ref "SW8")
      (value "FSM14JSMA")
      (footprint "eagle-import:FSM14JSMA")
      (libsource (lib "eagle-import") (part "PUSHBUTTON"))
    )
    (comp (ref "U6")
      (value "NETWORK_CONTROLLER")
      (footprint "eagle-import:PACKAGE_ATWINC3400-MR210XA")
      (libsource (lib "eagle-import") (part "NETWORK_CONTROLLER"))
    )
    (comp (ref "U7")
      (value "STM32F446RET6")
      (footprint "eagle-import:TRAY_STM32F446RET6")
      (libsource (lib "eagle-import") (part "STM32F446RET6"))
    )
    (comp (ref "U8")
      (value "SST26VF032B-104I/SM")
      (footprint "eagle-import:8-SOIJ")
      (libsource (lib "eagle-import") (part "SST26VF032B-104I/SM"))
    )
    (comp (ref "U9")
      (value "RT8289GSP")
      (footprint "eagle-import:8-SOIC")
      (libsource (lib "eagle-import") (part "RT8289GSP"))
    )
    (comp (ref "U10")
      (value "RT8289GSP")
      (footprint "eagle-import:8-SOIC")
      (libsource (lib "eagle-import") (part "RT8289GSP"))
    )
    (comp (ref "ULD3")
      (value "L196L-QYC-TR")
      (footprint "eagle-import:TAPE&REEL_DIODE")
      (libsource (lib "eagle-import") (part "LED"))
    )
    (comp (ref "ULD4")
      (value "L196L-OYC-TR")
      (footprint "eagle-import:TAPE&REEL_DIODE")
      (libsource (lib "eagle-import") (part "LED"))
    )
    (comp (ref "X3")
      (value "ASH7KW-32.768KHZ-L-T")
      (footprint "eagle-import:PACKAGE_ASH7KW")
      (libsource (lib "eagle-import") (part "ASH7KW-32.768KHZ-L-T"))
    )
    (comp (ref "X4")
      (value "FA-238")
      (footprint "eagle-import:PACKAGE_FA-23816.0000MB-K0")
      (libsource (lib "eagle-import") (part "FA-238"))
    )
  )
  (nets
    (net (code "1") (name "3V3") (class "Default")
      (node (ref "C46") (pin "P1") (pinfunction "P1_P1") (pintype "bidirectional"))
      (node (ref "C47") (pin "P1") (pinfunction "P1_P1") (pintype "bidirectional"))
      (node (ref "C48") (pin "P1") (pinfunction "P1_P1") (pintype "bidirectional"))
      (node (ref "C49") (pin "P2") (pinfunction "P2_P2") (pintype "bidirectional"))
      (node (ref "C50") (pin "P2") (pinfunction "P2_P2") (pintype "bidirectional"))
      (node (ref "C51") (pin "P1") (pinfunction "P1_P1") (pintype "bidirectional"))
      (node (ref "C56") (pin "P2") (pinfunction "P2_P2") (pintype "bidirectional"))
      (node (ref "C57") (pin "P2") (pinfunction "P2_P2") (pintype "bidirectional"))
      (node (ref "C58") (pin "P2") (pinfunction "P2_P2") (pintype "bidirectional"))
      (node (ref "C60") (pin "P2") (pinfunction "P2_P2") (pintype "bidirectional"))
      (node (ref "C61") (pin "P2") (pinfunction "P2_P2") (pintype "bidirectional"))
      (node (ref "C62") (pin "P1") (pinfunction "P1_P1") (pintype "bidirectional"))
      (node (ref "C63") (pin "P2") (pinfunction "P2_P2") (pintype "bidirectional"))
      (node (ref "C64") (pin "P2") (pinfunction "P2_P2") (pintype "bidirectional"))
      (node (ref "C65") (pin "P1") (pinfunction "P1_P1") (pintype "bidirectional"))
      (node (ref "F1") (pin "3") (pinfunction "3_3") (pintype "bidirectional"))
      (node (ref "L4") (pin "P1") (pinfunction "PIN1_P1") (pintype "bidirectional"))
      (node (ref "R29") (pin "P1") (pinfunction "P1_P1") (pintype "bidirectional"))
      (node (ref "R30") (pin "P1") (pinfunction "P1_P1") (pintype "bidirectional"))
      (node (ref "R32") (pin "P1") (pinfunction "P1_P1") (pintype "bidirectional"))
      (node (ref "R36") (pin "P2") (pinfunction "P2_P2") (pintype "bidirectional"))
      (node (ref "R40") (pin "P2") (pinfunction "P2_P2") (pintype "bidirectional"))
      (node (ref "R41") (pin "P2") (pinfunction "P2_P2") (pintype "bidirectional"))
      (node (ref "R42") (pin "P2") (pinfunction "P2_P2") (pintype "bidirectional"))
      (node (ref "R43") (pin "P2") (pinfunction "P2_P2") (pintype "bidirectional"))
      (node (ref "R44") (pin "P1") (pinfunction "P1_P1") (pintype "bidirectional"))
      (node (ref "U6") (pin "VBAT") (pinfunction "VBAT_VBAT") (pintype "bidirectional"))
      (node (ref "U6") (pin "VDDIO") (pinfunction "VDDIO_VDDIO") (pintype "bidirectional"))
      (node (ref "U7") (pin "VBAT") (pinfunction "VBAT_VBAT") (pintype "bidirectional"))
      (node (ref "U7") (pin "VDD1") (pinfunction "VDD_VDD1") (pintype "bidirectional"))
      (node (ref "U7") (pin "VDD2") (pinfunction "VDD_VDD2") (pintype "bidirectional"))
      (node (ref "U7") (pin "VDD3") (pinfunction "VDD_VDD3") (pintype "bidirectional"))
      (node (ref "U7") (pin "VDDUSB") (pinfunction "VDDUSB_VDDUSB") (pintype "bidirectional"))
      (node (ref "U8") (pin "HOLD") (pinfunction "HOLD_HOLD") (pintype "bidirectional"))
      (node (ref "U8") (pin "VDD") (pinfunction "VDD_VDD") (pintype "bidirectional"))
      (node (ref "X3") (pin "OE") (pinfunction "OE_OE") (pintype "bidirectional"))
      (node (ref "X3") (pin "VDD") (pinfunction "VDD_VDD") (pintype "bidirectional"))
    )
    (net (code "2") (name "5V") (class "Default")
      (node (ref "C1") (pin "P2") (pinfunction "P2_P2") (pintype "bidirectional"))
      (node (ref "C10") (pin "P2") (pinfunction "P2_P2") (pintype "bidirectional"))
      (node (ref "C11") (pin "P2") (pinfunction "P2_P2") (pintype "bidirectional"))
      (node (ref "C12") (pin "P2") (pinfunction "P2_P2") (pintype "bidirectional"))
      (node (ref "C13") (pin "P2") (pinfunction "P2_P2") (pintype "bidirectional"))
      (node (ref "C14") (pin "P2") (pinfunction "P2_P2") (pintype "bidirectional"))
      (node (ref "C15") (pin "P2") (pinfunction "P2_P2") (pintype "bidirectional"))
      (node (ref "C16") (pin "P2") (pinfunction "P2_P2") (pintype "bidirectional"))
      (node (ref "C17") (pin "P2") (pinfunction "P2_P2") (pintype "bidirectional"))
      (node (ref "C18") (pin "P2") (pinfunction "P2_P2") (pintype "bidirectional"))
      (node (ref "C19") (pin "P2") (pinfunction "P2_P2") (pintype "bidirectional"))
      (node (ref "C2") (pin "P2") (pinfunction "P2_P2") (pintype "bidirectional"))
      (node (ref "C20") (pin "P2") (pinfunction "P2_P2") (pintype "bidirectional"))
      (node (ref "C21") (pin "P2") (pinfunction "P2_P2") (pintype "bidirectional"))
      (node (ref "C22") (pin "P2") (pinfunction "P2_P2") (pintype "bidirectional"))
      (node (ref "C23") (pin "P2") (pinfunction "P2_P2") (pintype "bidirectional"))
      (node (ref "C24") (pin "P2") (pinfunction "P2_P2") (pintype "bidirectional"))
      (node (ref "C25") (pin "P2") (pinfunction "P2_P2") (pintype "bidirectional"))
      (node (ref "C26") (pin "P2") (pinfunction "P2_P2") (pintype "bidirectional"))
      (node (ref "C27") (pin "P2") (pinfunction "P2_P2") (pintype "bidirectional"))
      (node (ref "C28") (pin "P2") (pinfunction "P2_P2") (pintype "bidirectional"))
      (node (ref "C29") (pin "P2") (pinfunction "P2_P2") (pintype "bidirectional"))
      (node (ref "C3") (pin "P2") (pinfunction "P2_P2") (pintype "bidirectional"))
      (node (ref "C30") (pin "P2") (pinfunction "P2_P2") (pintype "bidirectional"))
      (node (ref "C31") (pin "P2") (pinfunction "P2_P2") (pintype "bidirectional"))
      (node (ref "C32") (pin "P2") (pinfunction "P2_P2") (pintype "bidirectional"))
      (node (ref "C33") (pin "P2") (pinfunction "P2_P2") (pintype "bidirectional"))
      (node (ref "C34") (pin "P2") (pinfunction "P2_P2") (pintype "bidirectional"))
      (node (ref "C35") (pin "P2") (pinfunction "P2_P2") (pintype "bidirectional"))
      (node (ref "C36") (pin "P2") (pinfunction "P2_P2") (pintype "bidirectional"))
      (node (ref "C37") (pin "P2") (pinfunction "P2_P2") (pintype "bidirectional"))
      (node (ref "C38") (pin "P2") (pinfunction "P2_P2") (pintype "bidirectional"))
      (node (ref "C39") (pin "P2") (pinfunction "P2_P2") (pintype "bidirectional"))
      (node (ref "C4") (pin "P2") (pinfunction "P2_P2") (pintype "bidirectional"))
      (node (ref "C40") (pin "P2") (pinfunction "P2_P2") (pintype "bidirectional"))
      (node (ref "C41") (pin "P2") (pinfunction "P2_P2") (pintype "bidirectional"))
      (node (ref "C42") (pin "P2") (pinfunction "P2_P2") (pintype "bidirectional"))
      (node (ref "C5") (pin "P2") (pinfunction "P2_P2") (pintype "bidirectional"))
      (node (ref "C6") (pin "P2") (pinfunction "P2_P2") (pintype "bidirectional"))
      (node (ref "C7") (pin "P2") (pinfunction "P2_P2") (pintype "bidirectional"))
      (node (ref "C73") (pin "P1") (pinfunction "P1_P1") (pintype "bidirectional"))
      (node (ref "C74") (pin "P1") (pinfunction "P1_P1") (pintype "bidirectional"))
      (node (ref "C75") (pin "P1") (pinfunction "P1_P1") (pintype "bidirectional"))
      (node (ref "C76") (pin "P1") (pinfunction "P1_P1") (pintype "bidirectional"))
      (node (ref "C8") (pin "P2") (pinfunction "P2_P2") (pintype "bidirectional"))
      (node (ref "C83") (pin "P1") (pinfunction "P1_P1") (pintype "bidirectional"))
      (node (ref "C84") (pin "P1") (pinfunction "P1_P1") (pintype "bidirectional"))
      (node (ref "C85") (pin "P1") (pinfunction "P1_P1") (pintype "bidirectional"))
      (node (ref "C86") (pin "P1") (pinfunction "P1_P1") (pintype "bidirectional"))
      (node (ref "C9") (pin "P2") (pinfunction "P2_P2") (pintype "bidirectional"))
      (node (ref "L5") (pin "PIN2") (pinfunction "PIN2_PIN2") (pintype "bidirectional"))
      (node (ref "L6") (pin "PIN2") (pinfunction "PIN2_PIN2") (pintype "bidirectional"))
      (node (ref "LED1") (pin "VDD") (pinfunction "VCC_VDD") (pintype "bidirectional"))
      (node (ref "LED10") (pin "VDD") (pinfunction "VCC_VDD") (pintype "bidirectional"))
      (node (ref "LED11") (pin "VDD") (pinfunction "VCC_VDD") (pintype "bidirectional"))
      (node (ref "LED12") (pin "VDD") (pinfunction "VCC_VDD") (pintype "bidirectional"))
      (node (ref "LED13") (pin "VDD") (pinfunction "VCC_VDD") (pintype "bidirectional"))
      (node (ref "LED14") (pin "VDD") (pinfunction "VCC_VDD") (pintype "bidirectional"))
      (node (ref "LED15") (pin "VDD") (pinfunction "VCC_VDD") (pintype "bidirectional"))
      (node (ref "LED16") (pin "VDD") (pinfunction "VCC_VDD") (pintype "bidirectional"))
      (node (ref "LED17") (pin "VDD") (pinfunction "VCC_VDD") (pintype "bidirectional"))
      (node (ref "LED18") (pin "VDD") (pinfunction "VCC_VDD") (pintype "bidirectional"))
      (node (ref "LED19") (pin "VDD") (pinfunction "VCC_VDD") (pintype "bidirectional"))
      (node (ref "LED2") (pin "VDD") (pinfunction "VCC_VDD") (pintype "bidirectional"))
      (node (ref "LED20") (pin "VDD") (pinfunction "VCC_VDD") (pintype "bidirectional"))
      (node (ref "LED21") (pin "VDD") (pinfunction "VCC_VDD") (pintype "bidirectional"))
      (node (ref "LED22") (pin "VDD") (pinfunction "VCC_VDD") (pintype "bidirectional"))
      (node (ref "LED23") (pin "VDD") (pinfunction "VCC_VDD") (pintype "bidirectional"))
      (node (ref "LED24") (pin "VDD") (pinfunction "VCC_VDD") (pintype "bidirectional"))
      (node (ref "LED25") (pin "VDD") (pinfunction "VCC_VDD") (pintype "bidirectional"))
      (node (ref "LED26") (pin "VDD") (pinfunction "VCC_VDD") (pintype "bidirectional"))
      (node (ref "LED27") (pin "VDD") (pinfunction "VCC_VDD") (pintype "bidirectional"))
      (node (ref "LED28") (pin "VDD") (pinfunction "VCC_VDD") (pintype "bidirectional"))
      (node (ref "LED29") (pin "VDD") (pinfunction "VCC_VDD") (pintype "bidirectional"))
      (node (ref "LED3") (pin "VDD") (pinfunction "VCC_VDD") (pintype "bidirectional"))
      (node (ref "LED30") (pin "VDD") (pinfunction "VCC_VDD") (pintype "bidirectional"))
      (node (ref "LED31") (pin "VDD") (pinfunction "VCC_VDD") (pintype "bidirectional"))
      (node (ref "LED32") (pin "VDD") (pinfunction "VCC_VDD") (pintype "bidirectional"))
      (node (ref "LED33") (pin "VDD") (pinfunction "VCC_VDD") (pintype "bidirectional"))
      (node (ref "LED34") (pin "VDD") (pinfunction "VCC_VDD") (pintype "bidirectional"))
      (node (ref "LED35") (pin "VDD") (pinfunction "VCC_VDD") (pintype "bidirectional"))
      (node (ref "LED36") (pin "VDD") (pinfunction "VCC_VDD") (pintype "bidirectional"))
      (node (ref "LED37") (pin "VDD") (pinfunction "VCC_VDD") (pintype "bidirectional"))
      (node (ref "LED38") (pin "VDD") (pinfunction "VCC_VDD") (pintype "bidirectional"))
      (node (ref "LED39") (pin "VDD") (pinfunction "VCC_VDD") (pintype "bidirectional"))
      (node (ref "LED4") (pin "VDD") (pinfunction "VCC_VDD") (pintype "bidirectional"))
      (node (ref "LED40") (pin "VDD") (pinfunction "VCC_VDD") (pintype "bidirectional"))
      (node (ref "LED41") (pin "VDD") (pinfunction "VCC_VDD") (pintype "bidirectional"))
      (node (ref "LED42") (pin "VDD") (pinfunction "VCC_VDD") (pintype "bidirectional"))
      (node (ref "LED5") (pin "VDD") (pinfunction "VCC_VDD") (pintype "bidirectional"))
      (node (ref "LED6") (pin "VDD") (pinfunction "VCC_VDD") (pintype "bidirectional"))
      (node (ref "LED7") (pin "VDD") (pinfunction "VCC_VDD") (pintype "bidirectional"))
      (node (ref "LED8") (pin "VDD") (pinfunction "VCC_VDD") (pintype "bidirectional"))
      (node (ref "LED9") (pin "VDD") (pinfunction "VCC_VDD") (pintype "bidirectional"))
      (node (ref "Q3") (pin "SOURCE") (pinfunction "SOURCE_SOURCE") (pintype "bidirectional"))
      (node (ref "Q5") (pin "SOURCE") (pinfunction "SOURCE_SOURCE") (pintype "bidirectional"))
      (node (ref "R2") (pin "P2") (pinfunction "P2_P2") (pintype "bidirectional"))
      (node (ref "R47") (pin "P2") (pinfunction "P2_P2") (pintype "bidirectional"))
      (node (ref "R53") (pin "P2") (pinfunction "P2_P2") (pintype "bidirectional"))
      (node (ref "R8") (pin "P2") (pinfunction "P2_P2") (pintype "bidirectional"))
    )
    (net (code "3") (name "12V") (class "Default")
      (node (ref "C77") (pin "P1") (pinfunction "P1_P1") (pintype "bidirectional"))
      (node (ref "C78") (pin "P1") (pinfunction "P1_P1") (pintype "bidirectional"))
      (node (ref "C79") (pin "P1") (pinfunction "P1_P1") (pintype "bidirectional"))
      (node (ref "C87") (pin "P1") (pinfunction "P1_P1") (pintype "bidirectional"))
      (node (ref "C88") (pin "P1") (pinfunction "P1_P1") (pintype "bidirectional"))
      (node (ref "CON2") (pin "1") (pinfunction "1_1") (pintype "bidirectional"))
      (node (ref "R50") (pin "P1") (pinfunction "P1_P1") (pintype "bidirectional"))
      (node (ref "U10") (pin "VIN") (pinfunction "VIN_VIN") (pintype "bidirectional"))
      (node (ref "U9") (pin "VIN") (pinfunction "VIN_VIN") (pintype "bidirectional"))
    )
    (net (code "4") (name "BTN0") (class "Default")
      (node (ref "C66") (pin "P2") (pinfunction "P2_P2") (pintype "bidirectional"))
      (node (ref "R40") (pin "P1") (pinfunction "P1_P1") (pintype "bidirectional"))
      (node (ref "SW5") (pin "3") (pinfunction "PIN2_3") (pintype "bidirectional"))
      (node (ref "SW5") (pin "4") (pinfunction "PIN2_4") (pintype "bidirectional"))
      (node (ref "U7") (pin "PC0") (pinfunction "PC0_PC0") (pintype "bidirectional"))
    )
    (net (code "5") (name "BTN1") (class "Default")
      (node (ref "C67") (pin "P2") (pinfunction "P2_P2") (pintype "bidirectional"))
      (node (ref "R41") (pin "P1") (pinfunction "P1_P1") (pintype "bidirectional"))
      (node (ref "SW6") (pin "3") (pinfunction "PIN2_3") (pintype "bidirectional"))
      (node (ref "SW6") (pin "4") (pinfunction "PIN2_4") (pintype "bidirectional"))
      (node (ref "U7") (pin "PC1") (pinfunction "PC1_PC1") (pintype "bidirectional"))
    )
    (net (code "6") (name "BTN2") (class "Default")
      (node (ref "C68") (pin "P2") (pinfunction "P2_P2") (pintype "bidirectional"))
      (node (ref "R42") (pin "P1") (pinfunction "P1_P1") (pintype "bidirectional"))
      (node (ref "SW7") (pin "3") (pinfunction "PIN2_3") (pintype "bidirectional"))
      (node (ref "SW7") (pin "4") (pinfunction "PIN2_4") (pintype "bidirectional"))
      (node (ref "U7") (pin "PC2") (pinfunction "PC2_PC2") (pintype "bidirectional"))
      (node (ref "U7") (pin "PC3") (pinfunction "PC3_PC3") (pintype "bidirectional"))
    )
    (net (code "7") (name "BTN3") (class "Default")
      (node (ref "C69") (pin "P2") (pinfunction "P2_P2") (pintype "bidirectional"))
      (node (ref "R43") (pin "P1") (pinfunction "P1_P1") (pintype "bidirectional"))
      (node (ref "SW8") (pin "3") (pinfunction "PIN2_3") (pintype "bidirectional"))
      (node (ref "SW8") (pin "4") (pinfunction "PIN2_4") (pintype "bidirectional"))
    )
    (net (code "8") (name "CHG-EN") (class "Default")
      (node (ref "C70") (pin "P1") (pinfunction "P1_P1") (pintype "bidirectional"))
      (node (ref "C80") (pin "P1") (pinfunction "P1_P1") (pintype "bidirectional"))
      (node (ref "R34") (pin "P1") (pinfunction "P1_P1") (pintype "bidirectional"))
      (node (ref "R44") (pin "P2") (pinfunction "P2_P2") (pintype "bidirectional"))
      (node (ref "R50") (pin "P2") (pinfunction "P2_P2") (pintype "bidirectional"))
      (node (ref "R56") (pin "P1") (pinfunction "P1_P1") (pintype "bidirectional"))
      (node (ref "U10") (pin "EN") (pinfunction "EN_EN") (pintype "bidirectional"))
      (node (ref "U9") (pin "EN") (pinfunction "EN_EN") (pintype "bidirectional"))
    )
    (net (code "9") (name "CI1") (class "Default")
      (node (ref "LED1") (pin "CI") (pinfunction "CI_CI") (pintype "bidirectional"))
      (node (ref "R11") (pin "P1") (pinfunction "P1_P1") (pintype "bidirectional"))
      (node (ref "R12") (pin "P1") (pinfunction "P1_P1") (pintype "bidirectional"))
      (node (ref "R13") (pin "P1") (pinfunction "P1_P1") (pintype "bidirectional"))
    )
    (net (code "10") (name "CO1") (class "Default")
      (node (ref "LED7") (pin "CO") (pinfunction "CO_CO") (pintype "bidirectional"))
      (node (ref "LED8") (pin "CI") (pinfunction "CI_CI") (pintype "bidirectional"))
    )
    (net (code "11") (name "CO2") (class "Default")
      (node (ref "LED14") (pin "CO") (pinfunction "CO_CO") (pintype "bidirectional"))
      (node (ref "LED15") (pin "CI") (pinfunction "CI_CI") (pintype "bidirectional"))
    )
    (net (code "12") (name "CO3") (class "Default")
      (node (ref "LED21") (pin "CO") (pinfunction "CO_CO") (pintype "bidirectional"))
      (node (ref "LED22") (pin "CI") (pinfunction "CI_CI") (pintype "bidirectional"))
    )
    (net (code "13") (name "CO4") (class "Default")
      (node (ref "LED28") (pin "CO") (pinfunction "CO_CO") (pintype "bidirectional"))
      (node (ref "LED29") (pin "CI") (pinfunction "CI_CI") (pintype "bidirectional"))
    )
    (net (code "14") (name "CO5") (class "Default")
      (node (ref "LED35") (pin "CO") (pinfunction "CO_CO") (pintype "bidirectional"))
      (node (ref "LED36") (pin "CI") (pinfunction "CI_CI") (pintype "bidirectional"))
    )
    (net (code "15") (name "CO6") (class "Default")
      (node (ref "LED42") (pin "CO") (pinfunction "CO_CO") (pintype "bidirectional"))
    )
    (net (code "16") (name "DI1") (class "Default")
      (node (ref "LED1") (pin "DI") (pinfunction "DI_DI") (pintype "bidirectional"))
      (node (ref "R5") (pin "P1") (pinfunction "P1_P1") (pintype "bidirectional"))
      (node (ref "R6") (pin "P1") (pinfunction "P1_P1") (pintype "bidirectional"))
      (node (ref "R7") (pin "P1") (pinfunction "P1_P1") (pintype "bidirectional"))
    )
    (net (code "17") (name "DO1") (class "Default")
      (node (ref "LED7") (pin "DO") (pinfunction "DO_DO") (pintype "bidirectional"))
      (node (ref "LED8") (pin "DI") (pinfunction "DI_DI") (pintype "bidirectional"))
    )
    (net (code "18") (name "DO2") (class "Default")
      (node (ref "LED14") (pin "DO") (pinfunction "DO_DO") (pintype "bidirectional"))
      (node (ref "LED15") (pin "DI") (pinfunction "DI_DI") (pintype "bidirectional"))
    )
    (net (code "19") (name "DO3") (class "Default")
      (node (ref "LED21") (pin "DO") (pinfunction "DO_DO") (pintype "bidirectional"))
      (node (ref "LED22") (pin "DI") (pinfunction "DI_DI") (pintype "bidirectional"))
    )
    (net (code "20") (name "DO4") (class "Default")
      (node (ref "LED28") (pin "DO") (pinfunction "DO_DO") (pintype "bidirectional"))
      (node (ref "LED29") (pin "DI") (pinfunction "DI_DI") (pintype "bidirectional"))
    )
    (net (code "21") (name "DO5") (class "Default")
      (node (ref "LED35") (pin "DO") (pinfunction "DO_DO") (pintype "bidirectional"))
      (node (ref "LED36") (pin "DI") (pinfunction "DI_DI") (pintype "bidirectional"))
    )
    (net (code "22") (name "DO6") (class "Default")
      (node (ref "LED42") (pin "DO") (pinfunction "DO_DO") (pintype "bidirectional"))
    )
    (net (code "23") (name "F446-DRX") (class "Default")
      (node (ref "F1") (pin "10") (pinfunction "10_10") (pintype "bidirectional"))
      (node (ref "U7") (pin "PB7") (pinfunction "PB7_PB7") (pintype "bidirectional"))
    )
    (net (code "24") (name "F446-DTX") (class "Default")
      (node (ref "F1") (pin "9") (pinfunction "9_9") (pintype "bidirectional"))
      (node (ref "U7") (pin "PB6") (pinfunction "PB6_PB6") (pintype "bidirectional"))
    )
    (net (code "25") (name "F446-NRST") (class "Default")
      (node (ref "C52") (pin "P2") (pinfunction "P2_P2") (pintype "bidirectional"))
      (node (ref "F1") (pin "12") (pinfunction "12_12") (pintype "bidirectional"))
      (node (ref "R32") (pin "P2") (pinfunction "P2_P2") (pintype "bidirectional"))
      (node (ref "U7") (pin "NRST") (pinfunction "NRST_NRST") (pintype "bidirectional"))
    )
    (net (code "26") (name "F446-SWDCLK") (class "Default")
      (node (ref "F1") (pin "6") (pinfunction "6_6") (pintype "bidirectional"))
      (node (ref "U7") (pin "PA14") (pinfunction "PA14_PA14") (pintype "bidirectional"))
    )
    (net (code "27") (name "F446-SWDIO") (class "Default")
      (node (ref "F1") (pin "4") (pinfunction "4_4") (pintype "bidirectional"))
      (node (ref "U7") (pin "PA13") (pinfunction "PA13_PA13") (pintype "bidirectional"))
    )
    (net (code "28") (name "FLASH-CS") (class "Default")
      (node (ref "U7") (pin "PB12") (pinfunction "PB12_PB12") (pintype "bidirectional"))
      (node (ref "U8") (pin "CE") (pinfunction "CE_CE") (pintype "bidirectional"))
    )
    (net (code "29") (name "FLASH-MISO") (class "Default")
      (node (ref "U7") (pin "PB14") (pinfunction "PB14_PB14") (pintype "bidirectional"))
      (node (ref "U8") (pin "MISO") (pinfunction "MISO_MISO") (pintype "bidirectional"))
    )
    (net (code "30") (name "FLASH-MOSI") (class "Default")
      (node (ref "U7") (pin "PB15") (pinfunction "PB15_PB15") (pintype "bidirectional"))
      (node (ref "U8") (pin "MOSI") (pinfunction "MOSI_MOSI") (pintype "bidirectional"))
    )
    (net (code "31") (name "FLASH-SCK") (class "Default")
      (node (ref "U7") (pin "PB13") (pinfunction "PB13_PB13") (pintype "bidirectional"))
      (node (ref "U8") (pin "SCK") (pinfunction "SCK_SCK") (pintype "bidirectional"))
    )
    (net (code "32") (name "GND") (class "Default")
      (node (ref "C43") (pin "P1") (pinfunction "P1_P1") (pintype "bidirectional"))
      (node (ref "C46") (pin "P2") (pinfunction "P2_P2") (pintype "bidirectional"))
      (node (ref "C47") (pin "P2") (pinfunction "P2_P2") (pintype "bidirectional"))
      (node (ref "C48") (pin "P2") (pinfunction "P2_P2") (pintype "bidirectional"))
      (node (ref "C49") (pin "P1") (pinfunction "P1_P1") (pintype "bidirectional"))
      (node (ref "C50") (pin "P1") (pinfunction "P1_P1") (pintype "bidirectional"))
      (node (ref "C51") (pin "P2") (pinfunction "P2_P2") (pintype "bidirectional"))
      (node (ref "C52") (pin "P1") (pinfunction "P1_P1") (pintype "bidirectional"))
      (node (ref "C53") (pin "P1") (pinfunction "P1_P1") (pintype "bidirectional"))
      (node (ref "C54") (pin "P1") (pinfunction "P1_P1") (pintype "bidirectional"))
      (node (ref "C55") (pin "P1") (pinfunction "P1_P1") (pintype "bidirectional"))
      (node (ref "C56") (pin "P1") (pinfunction "P1_P1") (pintype "bidirectional"))
      (node (ref "C57") (pin "P1") (pinfunction "P1_P1") (pintype "bidirectional"))
      (node (ref "C58") (pin "P1") (pinfunction "P1_P1") (pintype "bidirectional"))
      (node (ref "C59") (pin "P1") (pinfunction "P1_P1") (pintype "bidirectional"))
      (node (ref "C60") (pin "P1") (pinfunction "P1_P1") (pintype "bidirectional"))
      (node (ref "C61") (pin "P1") (pinfunction "P1_P1") (pintype "bidirectional"))
      (node (ref "C62") (pin "P2") (pinfunction "P2_P2") (pintype "bidirectional"))
      (node (ref "C63") (pin "P1") (pinfunction "P1_P1") (pintype "bidirectional"))
      (node (ref "C64") (pin "P1") (pinfunction "P1_P1") (pintype "bidirectional"))
      (node (ref "C65") (pin "P2") (pinfunction "P2_P2") (pintype "bidirectional"))
      (node (ref "C66") (pin "P1") (pinfunction "P1_P1") (pintype "bidirectional"))
      (node (ref "C67") (pin "P1") (pinfunction "P1_P1") (pintype "bidirectional"))
      (node (ref "C68") (pin "P1") (pinfunction "P1_P1") (pintype "bidirectional"))
      (node (ref "C69") (pin "P1") (pinfunction "P1_P1") (pintype "bidirectional"))
      (node (ref "C70") (pin "P2") (pinfunction "P2_P2") (pintype "bidirectional"))
      (node (ref "C72") (pin "P2") (pinfunction "P2_P2") (pintype "bidirectional"))
      (node (ref "C73") (pin "P2") (pinfunction "P2_P2") (pintype "bidirectional"))
      (node (ref "C74") (pin "P2") (pinfunction "P2_P2") (pintype "bidirectional"))
      (node (ref "C75") (pin "P2") (pinfunction "P2_P2") (pintype "bidirectional"))
      (node (ref "C76") (pin "P2") (pinfunction "P2_P2") (pintype "bidirectional"))
      (node (ref "C77") (pin "P2") (pinfunction "P2_P2") (pintype "bidirectional"))
      (node (ref "C78") (pin "P2") (pinfunction "P2_P2") (pintype "bidirectional"))
      (node (ref "C79") (pin "P2") (pinfunction "P2_P2") (pintype "bidirectional"))
      (node (ref "C80") (pin "P2") (pinfunction "P2_P2") (pintype "bidirectional"))
      (node (ref "C82") (pin "P2") (pinfunction "P2_P2") (pintype "bidirectional"))
      (node (ref "C83") (pin "P2") (pinfunction "P2_P2") (pintype "bidirectional"))
      (node (ref "C84") (pin "P2") (pinfunction "P2_P2") (pintype "bidirectional"))
      (node (ref "C85") (pin "P2") (pinfunction "P2_P2") (pintype "bidirectional"))
      (node (ref "C86") (pin "P2") (pinfunction "P2_P2") (pintype "bidirectional"))
      (node (ref "C87") (pin "P2") (pinfunction "P2_P2") (pintype "bidirectional"))
      (node (ref "C88") (pin "P2") (pinfunction "P2_P2") (pintype "bidirectional"))
      (node (ref "CON2") (pin "2") (pinfunction "2_2") (pintype "bidirectional"))
      (node (ref "CON2") (pin "3") (pinfunction "3_3") (pintype "bidirectional"))
      (node (ref "D3") (pin "ANODE") (pinfunction "ANODE_ANODE") (pintype "bidirectional"))
      (node (ref "D4") (pin "ANODE") (pinfunction "ANODE_ANODE") (pintype "bidirectional"))
      (node (ref "F1") (pin "11") (pinfunction "11_11") (pintype "bidirectional"))
      (node (ref "F1") (pin "5") (pinfunction "5_5") (pintype "bidirectional"))
      (node (ref "F1") (pin "7") (pinfunction "7_7") (pintype "bidirectional"))
      (node (ref "Q1") (pin "DRAIN") (pinfunction "DRAIN_DRAIN") (pintype "bidirectional"))
      (node (ref "Q2") (pin "SOURCE") (pinfunction "SOURCE_SOURCE") (pintype "bidirectional"))
      (node (ref "Q4") (pin "SOURCE") (pinfunction "SOURCE_SOURCE") (pintype "bidirectional"))
      (node (ref "R1") (pin "P1") (pinfunction "P1_P1") (pintype "bidirectional"))
      (node (ref "R10") (pin "P2") (pinfunction "P2_P2") (pintype "bidirectional"))
      (node (ref "R3") (pin "P1") (pinfunction "P1_P1") (pintype "bidirectional"))
      (node (ref "R31") (pin "P1") (pinfunction "P1_P1") (pintype "bidirectional"))
      (node (ref "R35") (pin "P2") (pinfunction "P2_P2") (pintype "bidirectional"))
      (node (ref "R37") (pin "P1") (pinfunction "P1_P1") (pintype "bidirectional"))
      (node (ref "R38") (pin "P1") (pinfunction "P1_P1") (pintype "bidirectional"))
      (node (ref "R39") (pin "P1") (pinfunction "P1_P1") (pintype "bidirectional"))
      (node (ref "R4") (pin "P2") (pinfunction "P2_P2") (pintype "bidirectional"))
      (node (ref "R46") (pin "P1") (pinfunction "P1_P1") (pintype "bidirectional"))
      (node (ref "R52") (pin "P1") (pinfunction "P1_P1") (pintype "bidirectional"))
      (node (ref "R56") (pin "P2") (pinfunction "P2_P2") (pintype "bidirectional"))
      (node (ref "R9") (pin "P1") (pinfunction "P1_P1") (pintype "bidirectional"))
      (node (ref "SW5") (pin "1") (pinfunction "PIN1_1") (pintype "bidirectional"))
      (node (ref "SW5") (pin "2") (pinfunction "PIN1_2") (pintype "bidirectional"))
      (node (ref "SW6") (pin "1") (pinfunction "PIN1_1") (pintype "bidirectional"))
      (node (ref "SW6") (pin "2") (pinfunction "PIN1_2") (pintype "bidirectional"))
      (node (ref "SW7") (pin "1") (pinfunction "PIN1_1") (pintype "bidirectional"))
      (node (ref "SW7") (pin "2") (pinfunction "PIN1_2") (pintype "bidirectional"))
      (node (ref "SW8") (pin "1") (pinfunction "PIN1_1") (pintype "bidirectional"))
      (node (ref "SW8") (pin "2") (pinfunction "PIN1_2") (pintype "bidirectional"))
      (node (ref "U10") (pin "GND1") (pinfunction "GND_GND1") (pintype "bidirectional"))
      (node (ref "U10") (pin "GND2") (pinfunction "GND_GND2") (pintype "bidirectional"))
      (node (ref "U6") (pin "GND@1") (pinfunction "GND_GND@1") (pintype "bidirectional"))
      (node (ref "U6") (pin "GND@2") (pinfunction "GND_GND@2") (pintype "bidirectional"))
      (node (ref "U6") (pin "GND@3") (pinfunction "GND_GND@3") (pintype "bidirectional"))
      (node (ref "U6") (pin "GND@4") (pinfunction "GND_GND@4") (pintype "bidirectional"))
      (node (ref "U6") (pin "GND@5") (pinfunction "GND_GND@5") (pintype "bidirectional"))
      (node (ref "U6") (pin "GND@6") (pinfunction "GND_GND@6") (pintype "bidirectional"))
      (node (ref "U7") (pin "VSS1") (pinfunction "VSS_VSS1") (pintype "bidirectional"))
      (node (ref "U7") (pin "VSS2") (pinfunction "VSS_VSS2") (pintype "bidirectional"))
      (node (ref "U7") (pin "VSS3") (pinfunction "VSS_VSS3") (pintype "bidirectional"))
      (node (ref "U7") (pin "VSS4") (pinfunction "VSS_VSS4") (pintype "bidirectional"))
      (node (ref "U7") (pin "VSSA") (pinfunction "VSSA_VSSA") (pintype "bidirectional"))
      (node (ref "U8") (pin "VSS") (pinfunction "VSS_VSS") (pintype "bidirectional"))
      (node (ref "U8") (pin "WP") (pinfunction "WP_WP") (pintype "bidirectional"))
      (node (ref "U9") (pin "GND1") (pinfunction "GND_GND1") (pintype "bidirectional"))
      (node (ref "U9") (pin "GND2") (pinfunction "GND_GND2") (pintype "bidirectional"))
      (node (ref "X3") (pin "GND") (pinfunction "GND_GND") (pintype "bidirectional"))
      (node (ref "X4") (pin "2") (pinfunction "GND_2") (pintype "bidirectional"))
      (node (ref "X4") (pin "4") (pinfunction "GND_4") (pintype "bidirectional"))
    )
    (net (code "33") (name "LED-GND") (class "Default")
      (node (ref "C1") (pin "P1") (pinfunction "P1_P1") (pintype "bidirectional"))
      (node (ref "C10") (pin "P1") (pinfunction "P1_P1") (pintype "bidirectional"))
      (node (ref "C11") (pin "P1") (pinfunction "P1_P1") (pintype "bidirectional"))
      (node (ref "C12") (pin "P1") (pinfunction "P1_P1") (pintype "bidirectional"))
      (node (ref "C13") (pin "P1") (pinfunction "P1_P1") (pintype "bidirectional"))
      (node (ref "C14") (pin "P1") (pinfunction "P1_P1") (pintype "bidirectional"))
      (node (ref "C15") (pin "P1") (pinfunction "P1_P1") (pintype "bidirectional"))
      (node (ref "C16") (pin "P1") (pinfunction "P1_P1") (pintype "bidirectional"))
      (node (ref "C17") (pin "P1") (pinfunction "P1_P1") (pintype "bidirectional"))
      (node (ref "C18") (pin "P1") (pinfunction "P1_P1") (pintype "bidirectional"))
      (node (ref "C19") (pin "P1") (pinfunction "P1_P1") (pintype "bidirectional"))
      (node (ref "C2") (pin "P1") (pinfunction "P1_P1") (pintype "bidirectional"))
      (node (ref "C20") (pin "P1") (pinfunction "P1_P1") (pintype "bidirectional"))
      (node (ref "C21") (pin "P1") (pinfunction "P1_P1") (pintype "bidirectional"))
      (node (ref "C22") (pin "P1") (pinfunction "P1_P1") (pintype "bidirectional"))
      (node (ref "C23") (pin "P1") (pinfunction "P1_P1") (pintype "bidirectional"))
      (node (ref "C24") (pin "P1") (pinfunction "P1_P1") (pintype "bidirectional"))
      (node (ref "C25") (pin "P1") (pinfunction "P1_P1") (pintype "bidirectional"))
      (node (ref "C26") (pin "P1") (pinfunction "P1_P1") (pintype "bidirectional"))
      (node (ref "C27") (pin "P1") (pinfunction "P1_P1") (pintype "bidirectional"))
      (node (ref "C28") (pin "P1") (pinfunction "P1_P1") (pintype "bidirectional"))
      (node (ref "C29") (pin "P1") (pinfunction "P1_P1") (pintype "bidirectional"))
      (node (ref "C3") (pin "P1") (pinfunction "P1_P1") (pintype "bidirectional"))
      (node (ref "C30") (pin "P1") (pinfunction "P1_P1") (pintype "bidirectional"))
      (node (ref "C31") (pin "P1") (pinfunction "P1_P1") (pintype "bidirectional"))
      (node (ref "C32") (pin "P1") (pinfunction "P1_P1") (pintype "bidirectional"))
      (node (ref "C33") (pin "P1") (pinfunction "P1_P1") (pintype "bidirectional"))
      (node (ref "C34") (pin "P1") (pinfunction "P1_P1") (pintype "bidirectional"))
      (node (ref "C35") (pin "P1") (pinfunction "P1_P1") (pintype "bidirectional"))
      (node (ref "C36") (pin "P1") (pinfunction "P1_P1") (pintype "bidirectional"))
      (node (ref "C37") (pin "P1") (pinfunction "P1_P1") (pintype "bidirectional"))
      (node (ref "C38") (pin "P1") (pinfunction "P1_P1") (pintype "bidirectional"))
      (node (ref "C39") (pin "P1") (pinfunction "P1_P1") (pintype "bidirectional"))
      (node (ref "C4") (pin "P1") (pinfunction "P1_P1") (pintype "bidirectional"))
      (node (ref "C40") (pin "P1") (pinfunction "P1_P1") (pintype "bidirectional"))
      (node (ref "C41") (pin "P1") (pinfunction "P1_P1") (pintype "bidirectional"))
      (node (ref "C42") (pin "P1") (pinfunction "P1_P1") (pintype "bidirectional"))
      (node (ref "C5") (pin "P1") (pinfunction "P1_P1") (pintype "bidirectional"))
      (node (ref "C6") (pin "P1") (pinfunction "P1_P1") (pintype "bidirectional"))
      (node (ref "C7") (pin "P1") (pinfunction "P1_P1") (pintype "bidirectional"))
      (node (ref "C8") (pin "P1") (pinfunction "P1_P1") (pintype "bidirectional"))
      (node (ref "C9") (pin "P1") (pinfunction "P1_P1") (pintype "bidirectional"))
      (node (ref "LED1") (pin "GND") (pinfunction "GND_GND") (pintype "bidirectional"))
      (node (ref "LED10") (pin "GND") (pinfunction "GND_GND") (pintype "bidirectional"))
      (node (ref "LED11") (pin "GND") (pinfunction "GND_GND") (pintype "bidirectional"))
      (node (ref "LED12") (pin "GND") (pinfunction "GND_GND") (pintype "bidirectional"))
      (node (ref "LED13") (pin "GND") (pinfunction "GND_GND") (pintype "bidirectional"))
      (node (ref "LED14") (pin "GND") (pinfunction "GND_GND") (pintype "bidirectional"))
      (node (ref "LED15") (pin "GND") (pinfunction "GND_GND") (pintype "bidirectional"))
      (node (ref "LED16") (pin "GND") (pinfunction "GND_GND") (pintype "bidirectional"))
      (node (ref "LED17") (pin "GND") (pinfunction "GND_GND") (pintype "bidirectional"))
      (node (ref "LED18") (pin "GND") (pinfunction "GND_GND") (pintype "bidirectional"))
      (node (ref "LED19") (pin "GND") (pinfunction "GND_GND") (pintype "bidirectional"))
      (node (ref "LED2") (pin "GND") (pinfunction "GND_GND") (pintype "bidirectional"))
      (node (ref "LED20") (pin "GND") (pinfunction "GND_GND") (pintype "bidirectional"))
      (node (ref "LED21") (pin "GND") (pinfunction "GND_GND") (pintype "bidirectional"))
      (node (ref "LED22") (pin "GND") (pinfunction "GND_GND") (pintype "bidirectional"))
      (node (ref "LED23") (pin "GND") (pinfunction "GND_GND") (pintype "bidirectional"))
      (node (ref "LED24") (pin "GND") (pinfunction "GND_GND") (pintype "bidirectional"))
      (node (ref "LED25") (pin "GND") (pinfunction "GND_GND") (pintype "bidirectional"))
      (node (ref "LED26") (pin "GND") (pinfunction "GND_GND") (pintype "bidirectional"))
      (node (ref "LED27") (pin "GND") (pinfunction "GND_GND") (pintype "bidirectional"))
      (node (ref "LED28") (pin "GND") (pinfunction "GND_GND") (pintype "bidirectional"))
      (node (ref "LED29") (pin "GND") (pinfunction "GND_GND") (pintype "bidirectional"))
      (node (ref "LED3") (pin "GND") (pinfunction "GND_GND") (pintype "bidirectional"))
      (node (ref "LED30") (pin "GND") (pinfunction "GND_GND") (pintype "bidirectional"))
      (node (ref "LED31") (pin "GND") (pinfunction "GND_GND") (pintype "bidirectional"))
      (node (ref "LED32") (pin "GND") (pinfunction "GND_GND") (pintype "bidirectional"))
      (node (ref "LED33") (pin "GND") (pinfunction "GND_GND") (pintype "bidirectional"))
      (node (ref "LED34") (pin "GND") (pinfunction "GND_GND") (pintype "bidirectional"))
      (node (ref "LED35") (pin "GND") (pinfunction "GND_GND") (pintype "bidirectional"))
      (node (ref "LED36") (pin "GND") (pinfunction "GND_GND") (pintype "bidirectional"))
      (node (ref "LED37") (pin "GND") (pinfunction "GND_GND") (pintype "bidirectional"))
      (node (ref "LED38") (pin "GND") (pinfunction "GND_GND") (pintype "bidirectional"))
      (node (ref "LED39") (pin "GND") (pinfunction "GND_GND") (pintype "bidirectional"))
      (node (ref "LED4") (pin "GND") (pinfunction "GND_GND") (pintype "bidirectional"))
      (node (ref "LED40") (pin "GND") (pinfunction "GND_GND") (pintype "bidirectional"))
      (node (ref "LED41") (pin "GND") (pinfunction "GND_GND") (pintype "bidirectional"))
      (node (ref "LED42") (pin "GND") (pinfunction "GND_GND") (pintype "bidirectional"))
      (node (ref "LED5") (pin "GND") (pinfunction "GND_GND") (pintype "bidirectional"))
      (node (ref "LED6") (pin "GND") (pinfunction "GND_GND") (pintype "bidirectional"))
      (node (ref "LED7") (pin "GND") (pinfunction "GND_GND") (pintype "bidirectional"))
      (node (ref "LED8") (pin "GND") (pinfunction "GND_GND") (pintype "bidirectional"))
      (node (ref "LED9") (pin "GND") (pinfunction "GND_GND") (pintype "bidirectional"))
      (node (ref "Q1") (pin "SOURCE") (pinfunction "SOURCE_SOURCE") (pintype "bidirectional"))
    )
    (net (code "34") (name "LED-POW-EN") (class "Default")
      (node (ref "Q1") (pin "GATE") (pinfunction "GATE_GATE") (pintype "bidirectional"))
      (node (ref "R1") (pin "P2") (pinfunction "P2_P2") (pintype "bidirectional"))
    )
    (net (code "35") (name "LED-PWR-EN") (class "Default")
      (node (ref "U7") (pin "PB3") (pinfunction "PB3_PB3") (pintype "bidirectional"))
      (node (ref "U7") (pin "PB4") (pinfunction "PB4_PB4") (pintype "bidirectional"))
      (node (ref "U7") (pin "PB5") (pinfunction "PB5_PB5") (pintype "bidirectional"))
    )
    (net (code "36") (name "LEDS-DATA") (class "Default")
      (node (ref "Q2") (pin "GATE") (pinfunction "GATE_GATE") (pintype "bidirectional"))
      (node (ref "R3") (pin "P2") (pinfunction "P2_P2") (pintype "bidirectional"))
      (node (ref "R7") (pin "P2") (pinfunction "P2_P2") (pintype "bidirectional"))
    )
    (net (code "37") (name "LEDS-SCK") (class "Default")
      (node (ref "Q4") (pin "GATE") (pinfunction "GATE_GATE") (pintype "bidirectional"))
      (node (ref "R13") (pin "P2") (pinfunction "P2_P2") (pintype "bidirectional"))
      (node (ref "R9") (pin "P2") (pinfunction "P2_P2") (pintype "bidirectional"))
    )
    (net (code "38") (name "NTC") (class "Default")
      (node (ref "R36") (pin "P1") (pinfunction "P1_P1") (pintype "bidirectional"))
      (node (ref "R37") (pin "P2") (pinfunction "P2_P2") (pintype "bidirectional"))
      (node (ref "U7") (pin "PA0") (pinfunction "PA0_PA0") (pintype "bidirectional"))
    )
    (net (code "39") (name "Net-(C59-PadP2)") (class "Default")
      (node (ref "C59") (pin "P2") (pinfunction "P2_P2") (pintype "bidirectional"))
      (node (ref "U7") (pin "VCAP") (pinfunction "VCAP_VCAP") (pintype "bidirectional"))
    )
    (net (code "40") (name "Net-(C71-PadP1)") (class "Default")
      (node (ref "C71") (pin "P1") (pinfunction "P1_P1") (pintype "bidirectional"))
      (node (ref "R48") (pin "P2") (pinfunction "P2_P2") (pintype "bidirectional"))
    )
    (net (code "41") (name "Net-(C71-PadP2)") (class "Default")
      (node (ref "C71") (pin "P2") (pinfunction "P2_P2") (pintype "bidirectional"))
      (node (ref "D3") (pin "CATHODE") (pinfunction "CATHODE_CATHODE") (pintype "bidirectional"))
      (node (ref "L5") (pin "PIN1") (pinfunction "PIN1_PIN1") (pintype "bidirectional"))
      (node (ref "R49") (pin "P1") (pinfunction "P1_P1") (pintype "bidirectional"))
      (node (ref "U9") (pin "SW") (pinfunction "SW_SW") (pintype "bidirectional"))
    )
    (net (code "42") (name "Net-(C72-PadP1)") (class "Default")
      (node (ref "C72") (pin "P1") (pinfunction "P1_P1") (pintype "bidirectional"))
      (node (ref "R49") (pin "P2") (pinfunction "P2_P2") (pintype "bidirectional"))
    )
    (net (code "43") (name "Net-(C81-PadP1)") (class "Default")
      (node (ref "C81") (pin "P1") (pinfunction "P1_P1") (pintype "bidirectional"))
      (node (ref "R54") (pin "P2") (pinfunction "P2_P2") (pintype "bidirectional"))
    )
    (net (code "44") (name "Net-(C81-PadP2)") (class "Default")
      (node (ref "C81") (pin "P2") (pinfunction "P2_P2") (pintype "bidirectional"))
      (node (ref "D4") (pin "CATHODE") (pinfunction "CATHODE_CATHODE") (pintype "bidirectional"))
      (node (ref "L6") (pin "PIN1") (pinfunction "PIN1_PIN1") (pintype "bidirectional"))
      (node (ref "R55") (pin "P1") (pinfunction "P1_P1") (pintype "bidirectional"))
      (node (ref "U10") (pin "SW") (pinfunction "SW_SW") (pintype "bidirectional"))
    )
    (net (code "45") (name "Net-(C82-PadP1)") (class "Default")
      (node (ref "C82") (pin "P1") (pinfunction "P1_P1") (pintype "bidirectional"))
      (node (ref "R55") (pin "P2") (pinfunction "P2_P2") (pintype "bidirectional"))
    )
    (net (code "46") (name "Net-(L4-PIN2)") (class "Default")
      (node (ref "C55") (pin "P2") (pinfunction "P2_P2") (pintype "bidirectional"))
      (node (ref "L4") (pin "P2") (pinfunction "PIN2_P2") (pintype "bidirectional"))
      (node (ref "U7") (pin "VDDA") (pinfunction "VDDA_VDDA") (pintype "bidirectional"))
    )
    (net (code "47") (name "Net-(LED1-PadCO)") (class "Default")
      (node (ref "LED1") (pin "CO") (pinfunction "CO_CO") (pintype "bidirectional"))
      (node (ref "LED2") (pin "CI") (pinfunction "CI_CI") (pintype "bidirectional"))
    )
    (net (code "48") (name "Net-(LED1-PadDO)") (class "Default")
      (node (ref "LED1") (pin "DO") (pinfunction "DO_DO") (pintype "bidirectional"))
      (node (ref "LED2") (pin "DI") (pinfunction "DI_DI") (pintype "bidirectional"))
    )
    (net (code "49") (name "Net-(LED2-PadCO)") (class "Default")
      (node (ref "LED2") (pin "CO") (pinfunction "CO_CO") (pintype "bidirectional"))
      (node (ref "LED3") (pin "CI") (pinfunction "CI_CI") (pintype "bidirectional"))
    )
    (net (code "50") (name "Net-(LED2-PadDO)") (class "Default")
      (node (ref "LED2") (pin "DO") (pinfunction "DO_DO") (pintype "bidirectional"))
      (node (ref "LED3") (pin "DI") (pinfunction "DI_DI") (pintype "bidirectional"))
    )
    (net (code "51") (name "Net-(LED3-PadCO)") (class "Default")
      (node (ref "LED3") (pin "CO") (pinfunction "CO_CO") (pintype "bidirectional"))
      (node (ref "LED4") (pin "CI") (pinfunction "CI_CI") (pintype "bidirectional"))
    )
    (net (code "52") (name "Net-(LED3-PadDO)") (class "Default")
      (node (ref "LED3") (pin "DO") (pinfunction "DO_DO") (pintype "bidirectional"))
      (node (ref "LED4") (pin "DI") (pinfunction "DI_DI") (pintype "bidirectional"))
    )
    (net (code "53") (name "Net-(LED4-PadCO)") (class "Default")
      (node (ref "LED4") (pin "CO") (pinfunction "CO_CO") (pintype "bidirectional"))
      (node (ref "LED5") (pin "CI") (pinfunction "CI_CI") (pintype "bidirectional"))
    )
    (net (code "54") (name "Net-(LED4-PadDO)") (class "Default")
      (node (ref "LED4") (pin "DO") (pinfunction "DO_DO") (pintype "bidirectional"))
      (node (ref "LED5") (pin "DI") (pinfunction "DI_DI") (pintype "bidirectional"))
    )
    (net (code "55") (name "Net-(LED5-PadCO)") (class "Default")
      (node (ref "LED5") (pin "CO") (pinfunction "CO_CO") (pintype "bidirectional"))
      (node (ref "LED6") (pin "CI") (pinfunction "CI_CI") (pintype "bidirectional"))
    )
    (net (code "56") (name "Net-(LED5-PadDO)") (class "Default")
      (node (ref "LED5") (pin "DO") (pinfunction "DO_DO") (pintype "bidirectional"))
      (node (ref "LED6") (pin "DI") (pinfunction "DI_DI") (pintype "bidirectional"))
    )
    (net (code "57") (name "Net-(LED6-PadCO)") (class "Default")
      (node (ref "LED6") (pin "CO") (pinfunction "CO_CO") (pintype "bidirectional"))
      (node (ref "LED7") (pin "CI") (pinfunction "CI_CI") (pintype "bidirectional"))
    )
    (net (code "58") (name "Net-(LED6-PadDO)") (class "Default")
      (node (ref "LED6") (pin "DO") (pinfunction "DO_DO") (pintype "bidirectional"))
      (node (ref "LED7") (pin "DI") (pinfunction "DI_DI") (pintype "bidirectional"))
    )
    (net (code "59") (name "Net-(LED8-PadCO)") (class "Default")
      (node (ref "LED8") (pin "CO") (pinfunction "CO_CO") (pintype "bidirectional"))
      (node (ref "LED9") (pin "CI") (pinfunction "CI_CI") (pintype "bidirectional"))
    )
    (net (code "60") (name "Net-(LED8-PadDO)") (class "Default")
      (node (ref "LED8") (pin "DO") (pinfunction "DO_DO") (pintype "bidirectional"))
      (node (ref "LED9") (pin "DI") (pinfunction "DI_DI") (pintype "bidirectional"))
    )
    (net (code "61") (name "Net-(LED10-PadCI)") (class "Default")
      (node (ref "LED10") (pin "CI") (pinfunction "CI_CI") (pintype "bidirectional"))
      (node (ref "LED9") (pin "CO") (pinfunction "CO_CO") (pintype "bidirectional"))
    )
    (net (code "62") (name "Net-(LED10-PadCO)") (class "Default")
      (node (ref "LED10") (pin "CO") (pinfunction "CO_CO") (pintype "bidirectional"))
      (node (ref "LED11") (pin "CI") (pinfunction "CI_CI") (pintype "bidirectional"))
    )
    (net (code "63") (name "Net-(LED10-PadDI)") (class "Default")
      (node (ref "LED10") (pin "DI") (pinfunction "DI_DI") (pintype "bidirectional"))
      (node (ref "LED9") (pin "DO") (pinfunction "DO_DO") (pintype "bidirectional"))
    )
    (net (code "64") (name "Net-(LED10-PadDO)") (class "Default")
      (node (ref "LED10") (pin "DO") (pinfunction "DO_DO") (pintype "bidirectional"))
      (node (ref "LED11") (pin "DI") (pinfunction "DI_DI") (pintype "bidirectional"))
    )
    (net (code "65") (name "Net-(LED11-PadCO)") (class "Default")
      (node (ref "LED11") (pin "CO") (pinfunction "CO_CO") (pintype "bidirectional"))
      (node (ref "LED12") (pin "CI") (pinfunction "CI_CI") (pintype "bidirectional"))
    )
    (net (code "66") (name "Net-(LED11-PadDO)") (class "Default")
      (node (ref "LED11") (pin "DO") (pinfunction "DO_DO") (pintype "bidirectional"))
      (node (ref "LED12") (pin "DI") (pinfunction "DI_DI") (pintype "bidirectional"))
    )
    (net (code "67") (name "Net-(LED12-PadCO)") (class "Default")
      (node (ref "LED12") (pin "CO") (pinfunction "CO_CO") (pintype "bidirectional"))
      (node (ref "LED13") (pin "CI") (pinfunction "CI_CI") (pintype "bidirectional"))
    )
    (net (code "68") (name "Net-(LED12-PadDO)") (class "Default")
      (node (ref "LED12") (pin "DO") (pinfunction "DO_DO") (pintype "bidirectional"))
      (node (ref "LED13") (pin "DI") (pinfunction "DI_DI") (pintype "bidirectional"))
    )
    (net (code "69") (name "Net-(LED13-PadCO)") (class "Default")
      (node (ref "LED13") (pin "CO") (pinfunction "CO_CO") (pintype "bidirectional"))
      (node (ref "LED14") (pin "CI") (pinfunction "CI_CI") (pintype "bidirectional"))
    )
    (net (code "70") (name "Net-(LED13-PadDO)") (class "Default")
      (node (ref "LED13") (pin "DO") (pinfunction "DO_DO") (pintype "bidirectional"))
      (node (ref "LED14") (pin "DI") (pinfunction "DI_DI") (pintype "bidirectional"))
    )
    (net (code "71") (name "Net-(LED15-PadCO)") (class "Default")
      (node (ref "LED15") (pin "CO") (pinfunction "CO_CO") (pintype "bidirectional"))
      (node (ref "LED16") (pin "CI") (pinfunction "CI_CI") (pintype "bidirectional"))
    )
    (net (code "72") (name "Net-(LED15-PadDO)") (class "Default")
      (node (ref "LED15") (pin "DO") (pinfunction "DO_DO") (pintype "bidirectional"))
      (node (ref "LED16") (pin "DI") (pinfunction "DI_DI") (pintype "bidirectional"))
    )
    (net (code "73") (name "Net-(LED16-PadCO)") (class "Default")
      (node (ref "LED16") (pin "CO") (pinfunction "CO_CO") (pintype "bidirectional"))
      (node (ref "LED17") (pin "CI") (pinfunction "CI_CI") (pintype "bidirectional"))
    )
    (net (code "74") (name "Net-(LED16-PadDO)") (class "Default")
      (node (ref "LED16") (pin "DO") (pinfunction "DO_DO") (pintype "bidirectional"))
      (node (ref "LED17") (pin "DI") (pinfunction "DI_DI") (pintype "bidirectional"))
    )
    (net (code "75") (name "Net-(LED17-PadCO)") (class "Default")
      (node (ref "LED17") (pin "CO") (pinfunction "CO_CO") (pintype "bidirectional"))
      (node (ref "LED18") (pin "CI") (pinfunction "CI_CI") (pintype "bidirectional"))
    )
    (net (code "76") (name "Net-(LED17-PadDO)") (class "Default")
      (node (ref "LED17") (pin "DO") (pinfunction "DO_DO") (pintype "bidirectional"))
      (node (ref "LED18") (pin "DI") (pinfunction "DI_DI") (pintype "bidirectional"))
    )
    (net (code "77") (name "Net-(LED18-PadCO)") (class "Default")
      (node (ref "LED18") (pin "CO") (pinfunction "CO_CO") (pintype "bidirectional"))
      (node (ref "LED19") (pin "CI") (pinfunction "CI_CI") (pintype "bidirectional"))
    )
    (net (code "78") (name "Net-(LED18-PadDO)") (class "Default")
      (node (ref "LED18") (pin "DO") (pinfunction "DO_DO") (pintype "bidirectional"))
      (node (ref "LED19") (pin "DI") (pinfunction "DI_DI") (pintype "bidirectional"))
    )
    (net (code "79") (name "Net-(LED19-PadCO)") (class "Default")
      (node (ref "LED19") (pin "CO") (pinfunction "CO_CO") (pintype "bidirectional"))
      (node (ref "LED20") (pin "CI") (pinfunction "CI_CI") (pintype "bidirectional"))
    )
    (net (code "80") (name "Net-(LED19-PadDO)") (class "Default")
      (node (ref "LED19") (pin "DO") (pinfunction "DO_DO") (pintype "bidirectional"))
      (node (ref "LED20") (pin "DI") (pinfunction "DI_DI") (pintype "bidirectional"))
    )
    (net (code "81") (name "Net-(LED20-PadCO)") (class "Default")
      (node (ref "LED20") (pin "CO") (pinfunction "CO_CO") (pintype "bidirectional"))
      (node (ref "LED21") (pin "CI") (pinfunction "CI_CI") (pintype "bidirectional"))
    )
    (net (code "82") (name "Net-(LED20-PadDO)") (class "Default")
      (node (ref "LED20") (pin "DO") (pinfunction "DO_DO") (pintype "bidirectional"))
      (node (ref "LED21") (pin "DI") (pinfunction "DI_DI") (pintype "bidirectional"))
    )
    (net (code "83") (name "Net-(LED22-PadCO)") (class "Default")
      (node (ref "LED22") (pin "CO") (pinfunction "CO_CO") (pintype "bidirectional"))
      (node (ref "LED23") (pin "CI") (pinfunction "CI_CI") (pintype "bidirectional"))
    )
    (net (code "84") (name "Net-(LED22-PadDO)") (class "Default")
      (node (ref "LED22") (pin "DO") (pinfunction "DO_DO") (pintype "bidirectional"))
      (node (ref "LED23") (pin "DI") (pinfunction "DI_DI") (pintype "bidirectional"))
    )
    (net (code "85") (name "Net-(LED23-PadCO)") (class "Default")
      (node (ref "LED23") (pin "CO") (pinfunction "CO_CO") (pintype "bidirectional"))
      (node (ref "LED24") (pin "CI") (pinfunction "CI_CI") (pintype "bidirectional"))
    )
    (net (code "86") (name "Net-(LED23-PadDO)") (class "Default")
      (node (ref "LED23") (pin "DO") (pinfunction "DO_DO") (pintype "bidirectional"))
      (node (ref "LED24") (pin "DI") (pinfunction "DI_DI") (pintype "bidirectional"))
    )
    (net (code "87") (name "Net-(LED24-PadCO)") (class "Default")
      (node (ref "LED24") (pin "CO") (pinfunction "CO_CO") (pintype "bidirectional"))
      (node (ref "LED25") (pin "CI") (pinfunction "CI_CI") (pintype "bidirectional"))
    )
    (net (code "88") (name "Net-(LED24-PadDO)") (class "Default")
      (node (ref "LED24") (pin "DO") (pinfunction "DO_DO") (pintype "bidirectional"))
      (node (ref "LED25") (pin "DI") (pinfunction "DI_DI") (pintype "bidirectional"))
    )
    (net (code "89") (name "Net-(LED25-PadCO)") (class "Default")
      (node (ref "LED25") (pin "CO") (pinfunction "CO_CO") (pintype "bidirectional"))
      (node (ref "LED26") (pin "CI") (pinfunction "CI_CI") (pintype "bidirectional"))
    )
    (net (code "90") (name "Net-(LED25-PadDO)") (class "Default")
      (node (ref "LED25") (pin "DO") (pinfunction "DO_DO") (pintype "bidirectional"))
      (node (ref "LED26") (pin "DI") (pinfunction "DI_DI") (pintype "bidirectional"))
    )
    (net (code "91") (name "Net-(LED26-PadCO)") (class "Default")
      (node (ref "LED26") (pin "CO") (pinfunction "CO_CO") (pintype "bidirectional"))
      (node (ref "LED27") (pin "CI") (pinfunction "CI_CI") (pintype "bidirectional"))
    )
    (net (code "92") (name "Net-(LED26-PadDO)") (class "Default")
      (node (ref "LED26") (pin "DO") (pinfunction "DO_DO") (pintype "bidirectional"))
      (node (ref "LED27") (pin "DI") (pinfunction "DI_DI") (pintype "bidirectional"))
    )
    (net (code "93") (name "Net-(LED27-PadCO)") (class "Default")
      (node (ref "LED27") (pin "CO") (pinfunction "CO_CO") (pintype "bidirectional"))
      (node (ref "LED28") (pin "CI") (pinfunction "CI_CI") (pintype "bidirectional"))
    )
    (net (code "94") (name "Net-(LED27-PadDO)") (class "Default")
      (node (ref "LED27") (pin "DO") (pinfunction "DO_DO") (pintype "bidirectional"))
      (node (ref "LED28") (pin "DI") (pinfunction "DI_DI") (pintype "bidirectional"))
    )
    (net (code "95") (name "Net-(LED29-PadCO)") (class "Default")
      (node (ref "LED29") (pin "CO") (pinfunction "CO_CO") (pintype "bidirectional"))
      (node (ref "LED30") (pin "CI") (pinfunction "CI_CI") (pintype "bidirectional"))
    )
    (net (code "96") (name "Net-(LED29-PadDO)") (class "Default")
      (node (ref "LED29") (pin "DO") (pinfunction "DO_DO") (pintype "bidirectional"))
      (node (ref "LED30") (pin "DI") (pinfunction "DI_DI") (pintype "bidirectional"))
    )
    (net (code "97") (name "Net-(LED30-PadCO)") (class "Default")
      (node (ref "LED30") (pin "CO") (pinfunction "CO_CO") (pintype "bidirectional"))
      (node (ref "LED31") (pin "CI") (pinfunction "CI_CI") (pintype "bidirectional"))
    )
    (net (code "98") (name "Net-(LED30-PadDO)") (class "Default")
      (node (ref "LED30") (pin "DO") (pinfunction "DO_DO") (pintype "bidirectional"))
      (node (ref "LED31") (pin "DI") (pinfunction "DI_DI") (pintype "bidirectional"))
    )
    (net (code "99") (name "Net-(LED31-PadCO)") (class "Default")
      (node (ref "LED31") (pin "CO") (pinfunction "CO_CO") (pintype "bidirectional"))
      (node (ref "LED32") (pin "CI") (pinfunction "CI_CI") (pintype "bidirectional"))
    )
    (net (code "100") (name "Net-(LED31-PadDO)") (class "Default")
      (node (ref "LED31") (pin "DO") (pinfunction "DO_DO") (pintype "bidirectional"))
      (node (ref "LED32") (pin "DI") (pinfunction "DI_DI") (pintype "bidirectional"))
    )
    (net (code "101") (name "Net-(LED32-PadCO)") (class "Default")
      (node (ref "LED32") (pin "CO") (pinfunction "CO_CO") (pintype "bidirectional"))
      (node (ref "LED33") (pin "CI") (pinfunction "CI_CI") (pintype "bidirectional"))
    )
    (net (code "102") (name "Net-(LED32-PadDO)") (class "Default")
      (node (ref "LED32") (pin "DO") (pinfunction "DO_DO") (pintype "bidirectional"))
      (node (ref "LED33") (pin "DI") (pinfunction "DI_DI") (pintype "bidirectional"))
    )
    (net (code "103") (name "Net-(LED33-PadCO)") (class "Default")
      (node (ref "LED33") (pin "CO") (pinfunction "CO_CO") (pintype "bidirectional"))
      (node (ref "LED34") (pin "CI") (pinfunction "CI_CI") (pintype "bidirectional"))
    )
    (net (code "104") (name "Net-(LED33-PadDO)") (class "Default")
      (node (ref "LED33") (pin "DO") (pinfunction "DO_DO") (pintype "bidirectional"))
      (node (ref "LED34") (pin "DI") (pinfunction "DI_DI") (pintype "bidirectional"))
    )
    (net (code "105") (name "Net-(LED34-PadCO)") (class "Default")
      (node (ref "LED34") (pin "CO") (pinfunction "CO_CO") (pintype "bidirectional"))
      (node (ref "LED35") (pin "CI") (pinfunction "CI_CI") (pintype "bidirectional"))
    )
    (net (code "106") (name "Net-(LED34-PadDO)") (class "Default")
      (node (ref "LED34") (pin "DO") (pinfunction "DO_DO") (pintype "bidirectional"))
      (node (ref "LED35") (pin "DI") (pinfunction "DI_DI") (pintype "bidirectional"))
    )
    (net (code "107") (name "Net-(LED36-PadCO)") (class "Default")
      (node (ref "LED36") (pin "CO") (pinfunction "CO_CO") (pintype "bidirectional"))
      (node (ref "LED37") (pin "CI") (pinfunction "CI_CI") (pintype "bidirectional"))
    )
    (net (code "108") (name "Net-(LED36-PadDO)") (class "Default")
      (node (ref "LED36") (pin "DO") (pinfunction "DO_DO") (pintype "bidirectional"))
      (node (ref "LED37") (pin "DI") (pinfunction "DI_DI") (pintype "bidirectional"))
    )
    (net (code "109") (name "Net-(LED37-PadCO)") (class "Default")
      (node (ref "LED37") (pin "CO") (pinfunction "CO_CO") (pintype "bidirectional"))
      (node (ref "LED38") (pin "CI") (pinfunction "CI_CI") (pintype "bidirectional"))
    )
    (net (code "110") (name "Net-(LED37-PadDO)") (class "Default")
      (node (ref "LED37") (pin "DO") (pinfunction "DO_DO") (pintype "bidirectional"))
      (node (ref "LED38") (pin "DI") (pinfunction "DI_DI") (pintype "bidirectional"))
    )
    (net (code "111") (name "Net-(LED38-PadCO)") (class "Default")
      (node (ref "LED38") (pin "CO") (pinfunction "CO_CO") (pintype "bidirectional"))
      (node (ref "LED39") (pin "CI") (pinfunction "CI_CI") (pintype "bidirectional"))
    )
    (net (code "112") (name "Net-(LED38-PadDO)") (class "Default")
      (node (ref "LED38") (pin "DO") (pinfunction "DO_DO") (pintype "bidirectional"))
      (node (ref "LED39") (pin "DI") (pinfunction "DI_DI") (pintype "bidirectional"))
    )
    (net (code "113") (name "Net-(LED39-PadCO)") (class "Default")
      (node (ref "LED39") (pin "CO") (pinfunction "CO_CO") (pintype "bidirectional"))
      (node (ref "LED40") (pin "CI") (pinfunction "CI_CI") (pintype "bidirectional"))
    )
    (net (code "114") (name "Net-(LED39-PadDO)") (class "Default")
      (node (ref "LED39") (pin "DO") (pinfunction "DO_DO") (pintype "bidirectional"))
      (node (ref "LED40") (pin "DI") (pinfunction "DI_DI") (pintype "bidirectional"))
    )
    (net (code "115") (name "Net-(LED40-PadCO)") (class "Default")
      (node (ref "LED40") (pin "CO") (pinfunction "CO_CO") (pintype "bidirectional"))
      (node (ref "LED41") (pin "CI") (pinfunction "CI_CI") (pintype "bidirectional"))
    )
    (net (code "116") (name "Net-(LED40-PadDO)") (class "Default")
      (node (ref "LED40") (pin "DO") (pinfunction "DO_DO") (pintype "bidirectional"))
      (node (ref "LED41") (pin "DI") (pinfunction "DI_DI") (pintype "bidirectional"))
    )
    (net (code "117") (name "Net-(LED41-PadCO)") (class "Default")
      (node (ref "LED41") (pin "CO") (pinfunction "CO_CO") (pintype "bidirectional"))
      (node (ref "LED42") (pin "CI") (pinfunction "CI_CI") (pintype "bidirectional"))
    )
    (net (code "118") (name "Net-(LED41-PadDO)") (class "Default")
      (node (ref "LED41") (pin "DO") (pinfunction "DO_DO") (pintype "bidirectional"))
      (node (ref "LED42") (pin "DI") (pinfunction "DI_DI") (pintype "bidirectional"))
    )
    (net (code "119") (name "Net-(Q2-PadDRAIN)") (class "Default")
      (node (ref "Q2") (pin "DRAIN") (pinfunction "DRAIN_DRAIN") (pintype "bidirectional"))
      (node (ref "Q3") (pin "GATE") (pinfunction "GATE_GATE") (pintype "bidirectional"))
      (node (ref "R2") (pin "P1") (pinfunction "P1_P1") (pintype "bidirectional"))
      (node (ref "R6") (pin "P2") (pinfunction "P2_P2") (pintype "bidirectional"))
    )
    (net (code "120") (name "Net-(Q3-PadDRAIN)") (class "Default")
      (node (ref "Q3") (pin "DRAIN") (pinfunction "DRAIN_DRAIN") (pintype "bidirectional"))
      (node (ref "R4") (pin "P1") (pinfunction "P1_P1") (pintype "bidirectional"))
      (node (ref "R5") (pin "P2") (pinfunction "P2_P2") (pintype "bidirectional"))
    )
    (net (code "121") (name "Net-(Q4-PadDRAIN)") (class "Default")
      (node (ref "Q4") (pin "DRAIN") (pinfunction "DRAIN_DRAIN") (pintype "bidirectional"))
      (node (ref "Q5") (pin "GATE") (pinfunction "GATE_GATE") (pintype "bidirectional"))
      (node (ref "R12") (pin "P2") (pinfunction "P2_P2") (pintype "bidirectional"))
      (node (ref "R8") (pin "P1") (pinfunction "P1_P1") (pintype "bidirectional"))
    )
    (net (code "122") (name "Net-(Q5-PadDRAIN)") (class "Default")
      (node (ref "Q5") (pin "DRAIN") (pinfunction "DRAIN_DRAIN") (pintype "bidirectional"))
      (node (ref "R10") (pin "P1") (pinfunction "P1_P1") (pintype "bidirectional"))
      (node (ref "R11") (pin "P2") (pinfunction "P2_P2") (pintype "bidirectional"))
    )
    (net (code "123") (name "Net-(R29-PadP2)") (class "Default")
      (node (ref "R29") (pin "P2") (pinfunction "P2_P2") (pintype "bidirectional"))
      (node (ref "U6") (pin "SPI-CFG") (pinfunction "SPI-CFG_SPI-CFG") (pintype "bidirectional"))
    )
    (net (code "124") (name "Net-(R33-PadP2)") (class "Default")
      (node (ref "R33") (pin "P2") (pinfunction "P2_P2") (pintype "bidirectional"))
      (node (ref "U7") (pin "PH1") (pinfunction "PH1_PH1") (pintype "bidirectional"))
    )
    (net (code "125") (name "Net-(R34-PadP2)") (class "Default")
      (node (ref "R34") (pin "P2") (pinfunction "P2_P2") (pintype "bidirectional"))
      (node (ref "U7") (pin "PB10") (pinfunction "PB10_PB10") (pintype "bidirectional"))
    )
    (net (code "126") (name "Net-(R35-PadP1)") (class "Default")
      (node (ref "R35") (pin "P1") (pinfunction "P1_P1") (pintype "bidirectional"))
      (node (ref "U7") (pin "BOOT0") (pinfunction "BOOT0_BOOT0") (pintype "bidirectional"))
    )
    (net (code "127") (name "Net-(R38-PadP2)") (class "Default")
      (node (ref "R38") (pin "P2") (pinfunction "P2_P2") (pintype "bidirectional"))
      (node (ref "ULD3") (pin "CATHODE") (pinfunction "CATHODE_CATHODE") (pintype "bidirectional"))
    )
    (net (code "128") (name "Net-(R39-PadP2)") (class "Default")
      (node (ref "R39") (pin "P2") (pinfunction "P2_P2") (pintype "bidirectional"))
      (node (ref "ULD4") (pin "CATHODE") (pinfunction "CATHODE_CATHODE") (pintype "bidirectional"))
    )
    (net (code "129") (name "Net-(R45-PadP1)") (class "Default")
      (node (ref "R45") (pin "P1") (pinfunction "P1_P1") (pintype "bidirectional"))
      (node (ref "R46") (pin "P2") (pinfunction "P2_P2") (pintype "bidirectional"))
    )
    (net (code "130") (name "Net-(R45-PadP2)") (class "Default")
      (node (ref "R45") (pin "P2") (pinfunction "P2_P2") (pintype "bidirectional"))
      (node (ref "R47") (pin "P1") (pinfunction "P1_P1") (pintype "bidirectional"))
      (node (ref "U9") (pin "FB") (pinfunction "FB_FB") (pintype "bidirectional"))
    )
    (net (code "131") (name "Net-(R48-PadP1)") (class "Default")
      (node (ref "R48") (pin "P1") (pinfunction "P1_P1") (pintype "bidirectional"))
      (node (ref "U9") (pin "BOOT") (pinfunction "BOOT_BOOT") (pintype "bidirectional"))
    )
    (net (code "132") (name "Net-(R51-PadP1)") (class "Default")
      (node (ref "R51") (pin "P1") (pinfunction "P1_P1") (pintype "bidirectional"))
      (node (ref "R52") (pin "P2") (pinfunction "P2_P2") (pintype "bidirectional"))
    )
    (net (code "133") (name "Net-(R51-PadP2)") (class "Default")
      (node (ref "R51") (pin "P2") (pinfunction "P2_P2") (pintype "bidirectional"))
      (node (ref "R53") (pin "P1") (pinfunction "P1_P1") (pintype "bidirectional"))
      (node (ref "U10") (pin "FB") (pinfunction "FB_FB") (pintype "bidirectional"))
    )
    (net (code "134") (name "Net-(R54-PadP1)") (class "Default")
      (node (ref "R54") (pin "P1") (pinfunction "P1_P1") (pintype "bidirectional"))
      (node (ref "U10") (pin "BOOT") (pinfunction "BOOT_BOOT") (pintype "bidirectional"))
    )
    (net (code "135") (name "Net-(U6-PadRTC-CLK)") (class "Default")
      (node (ref "U6") (pin "RTC-CLK") (pinfunction "RTC-CLK_RTC-CLK") (pintype "bidirectional"))
      (node (ref "X3") (pin "OUT") (pinfunction "OUT_OUT") (pintype "bidirectional"))
    )
    (net (code "136") (name "Net-(X4-PIN1)") (class "Default")
      (node (ref "C53") (pin "P2") (pinfunction "P2_P2") (pintype "bidirectional"))
      (node (ref "R33") (pin "P1") (pinfunction "P1_P1") (pintype "bidirectional"))
      (node (ref "X4") (pin "1") (pinfunction "PIN1_1") (pintype "bidirectional"))
    )
    (net (code "137") (name "Net-(X4-PIN2)") (class "Default")
      (node (ref "C54") (pin "P2") (pinfunction "P2_P2") (pintype "bidirectional"))
      (node (ref "U7") (pin "PH0") (pinfunction "PH0_PH0") (pintype "bidirectional"))
      (node (ref "X4") (pin "3") (pinfunction "PIN2_3") (pintype "bidirectional"))
    )
    (net (code "138") (name "ULD0") (class "Default")
      (node (ref "U7") (pin "PB8") (pinfunction "PB8_PB8") (pintype "bidirectional"))
      (node (ref "ULD3") (pin "ANODE") (pinfunction "ANODE_ANODE") (pintype "bidirectional"))
    )
    (net (code "139") (name "ULD1") (class "Default")
      (node (ref "U7") (pin "PB9") (pinfunction "PB9_PB9") (pintype "bidirectional"))
      (node (ref "ULD4") (pin "ANODE") (pinfunction "ANODE_ANODE") (pintype "bidirectional"))
    )
    (net (code "140") (name "WIFI-CS") (class "Default")
      (node (ref "U6") (pin "SPI-SSN") (pinfunction "SPI-SSN_SPI-SSN") (pintype "bidirectional"))
      (node (ref "U7") (pin "PA4") (pinfunction "PA4_PA4") (pintype "bidirectional"))
    )
    (net (code "141") (name "WIFI-EN") (class "Default")
      (node (ref "R31") (pin "P2") (pinfunction "P2_P2") (pintype "bidirectional"))
      (node (ref "U6") (pin "CHIP-EN") (pinfunction "CHIP-EN_CHIP-EN") (pintype "bidirectional"))
      (node (ref "U7") (pin "PC4") (pinfunction "PC4_PC4") (pintype "bidirectional"))
    )
    (net (code "142") (name "WIFI-IRQ") (class "Default")
      (node (ref "U6") (pin "IRQN") (pinfunction "IRQN_IRQN") (pintype "bidirectional"))
      (node (ref "U7") (pin "PB0") (pinfunction "PB0_PB0") (pintype "bidirectional"))
    )
    (net (code "143") (name "WIFI-MISO") (class "Default")
      (node (ref "U6") (pin "SPI-MISO") (pinfunction "SPI-MISO_SPI-MISO") (pintype "bidirectional"))
      (node (ref "U7") (pin "PA6") (pinfunction "PA6_PA6") (pintype "bidirectional"))
    )
    (net (code "144") (name "WIFI-MOSI") (class "Default")
      (node (ref "U6") (pin "SPI-MOSI") (pinfunction "SPI-MOSI_SPI-MOSI") (pintype "bidirectional"))
      (node (ref "U7") (pin "PA7") (pinfunction "PA7_PA7") (pintype "bidirectional"))
    )
    (net (code "145") (name "WIFI-RESET") (class "Default")
      (node (ref "C43") (pin "P2") (pinfunction "P2_P2") (pintype "bidirectional"))
      (node (ref "R30") (pin "P2") (pinfunction "P2_P2") (pintype "bidirectional"))
      (node (ref "U6") (pin "RESETN") (pinfunction "RESETN_RESETN") (pintype "bidirectional"))
      (node (ref "U7") (pin "PC5") (pinfunction "PC5_PC5") (pintype "bidirectional"))
    )
    (net (code "146") (name "WIFI-SCK") (class "Default")
      (node (ref "U6") (pin "SPI-SCK") (pinfunction "SPI-SCK_SPI-SCK") (pintype "bidirectional"))
      (node (ref "U7") (pin "PA5") (pinfunction "PA5_PA5") (pintype "bidirectional"))
    )
    (net (code "147") (name "unconnected-(F1-Pad1)") (class "Default")
      (node (ref "F1") (pin "1") (pinfunction "1_1") (pintype "bidirectional"))
    )
    (net (code "148") (name "unconnected-(F1-Pad2)") (class "Default")
      (node (ref "F1") (pin "2") (pinfunction "2_2") (pintype "bidirectional"))
    )
    (net (code "149") (name "unconnected-(F1-Pad8)") (class "Default")
      (node (ref "F1") (pin "8") (pinfunction "8_8") (pintype "bidirectional"))
    )
    (net (code "150") (name "unconnected-(F1-Pad13)") (class "Default")
      (node (ref "F1") (pin "13") (pinfunction "13_13") (pintype "bidirectional"))
    )
    (net (code "151") (name "unconnected-(F1-Pad14)") (class "Default")
      (node (ref "F1") (pin "14") (pinfunction "14_14") (pintype "bidirectional"))
    )
    (net (code "152") (name "unconnected-(U6-NC-PadNC@1)") (class "Default")
      (node (ref "U6") (pin "NC@1") (pinfunction "NC_NC@1") (pintype "bidirectional"))
    )
    (net (code "153") (name "unconnected-(U6-NC-PadNC@2)") (class "Default")
      (node (ref "U6") (pin "NC@2") (pinfunction "NC_NC@2") (pintype "bidirectional"))
    )
    (net (code "154") (name "unconnected-(U6-NC-PadNC@3)") (class "Default")
      (node (ref "U6") (pin "NC@3") (pinfunction "NC_NC@3") (pintype "bidirectional"))
    )
    (net (code "155") (name "unconnected-(U6-NC-PadNC@4)") (class "Default")
      (node (ref "U6") (pin "NC@4") (pinfunction "NC_NC@4") (pintype "bidirectional"))
    )
    (net (code "156") (name "unconnected-(U6-PadBT-RXD)") (class "Default")
      (node (ref "U6") (pin "BT-RXD") (pinfunction "BT-RXD_BT-RXD") (pintype "bidirectional"))
    )
    (net (code "157") (name "unconnected-(U6-PadBT-TXD)") (class "Default")
      (node (ref "U6") (pin "BT-TXD") (pinfunction "BT-TXD_BT-TXD") (pintype "bidirectional"))
    )
    (net (code "158") (name "unconnected-(U6-PadGPIO3)") (class "Default")
      (node (ref "U6") (pin "GPIO3") (pinfunction "GPIO3_GPIO3") (pintype "bidirectional"))
    )
    (net (code "159") (name "unconnected-(U6-PadGPIO4)") (class "Default")
      (node (ref "U6") (pin "GPIO4") (pinfunction "GPIO4_GPIO4") (pintype "bidirectional"))
    )
    (net (code "160") (name "unconnected-(U6-PadGPIO7)") (class "Default")
      (node (ref "U6") (pin "GPIO7") (pinfunction "GPIO7_GPIO7") (pintype "bidirectional"))
    )
    (net (code "161") (name "unconnected-(U6-PadGPIO8)") (class "Default")
      (node (ref "U6") (pin "GPIO8") (pinfunction "GPIO8_GPIO8") (pintype "bidirectional"))
    )
    (net (code "162") (name "unconnected-(U6-PadGPIO17)") (class "Default")
      (node (ref "U6") (pin "GPIO17") (pinfunction "GPIO17_GPIO17") (pintype "bidirectional"))
    )
    (net (code "163") (name "unconnected-(U6-PadGPIO18)") (class "Default")
      (node (ref "U6") (pin "GPIO18") (pinfunction "GPIO18_GPIO18") (pintype "bidirectional"))
    )
    (net (code "164") (name "unconnected-(U6-PadGPIO19)") (class "Default")
      (node (ref "U6") (pin "GPIO19") (pinfunction "GPIO19_GPIO19") (pintype "bidirectional"))
    )
    (net (code "165") (name "unconnected-(U6-PadGPIO20)") (class "Default")
      (node (ref "U6") (pin "GPIO20") (pinfunction "GPIO20_GPIO20") (pintype "bidirectional"))
    )
    (net (code "166") (name "unconnected-(U6-PadI2C-SCLM)") (class "Default")
      (node (ref "U6") (pin "I2C-SCLM") (pinfunction "I2C-SCLM_I2C-SCLM") (pintype "bidirectional"))
    )
    (net (code "167") (name "unconnected-(U6-PadI2C-SCLS)") (class "Default")
      (node (ref "U6") (pin "I2C-SCLS") (pinfunction "I2C-SCLS_I2C-SCLS") (pintype "bidirectional"))
    )
    (net (code "168") (name "unconnected-(U6-PadI2C-SDAM)") (class "Default")
      (node (ref "U6") (pin "I2C-SDAM") (pinfunction "I2C-SDAM_I2C-SDAM") (pintype "bidirectional"))
    )
    (net (code "169") (name "unconnected-(U6-PadI2C-SDAS)") (class "Default")
      (node (ref "U6") (pin "I2C-SDAS") (pinfunction "I2C-SDAS_I2C-SDAS") (pintype "bidirectional"))
    )
    (net (code "170") (name "unconnected-(U6-PadUART-RXD)") (class "Default")
      (node (ref "U6") (pin "UART-RXD") (pinfunction "UART-RXD_UART-RXD") (pintype "bidirectional"))
    )
    (net (code "171") (name "unconnected-(U6-PadUART-TXD)") (class "Default")
      (node (ref "U6") (pin "UART-TXD") (pinfunction "UART-TXD_UART-TXD") (pintype "bidirectional"))
    )
    (net (code "172") (name "unconnected-(U7-PadPA1)") (class "Default")
      (node (ref "U7") (pin "PA1") (pinfunction "PA1_PA1") (pintype "bidirectional"))
    )
    (net (code "173") (name "unconnected-(U7-PadPA2)") (class "Default")
      (node (ref "U7") (pin "PA2") (pinfunction "PA2_PA2") (pintype "bidirectional"))
    )
    (net (code "174") (name "unconnected-(U7-PadPA3)") (class "Default")
      (node (ref "U7") (pin "PA3") (pinfunction "PA3_PA3") (pintype "bidirectional"))
    )
    (net (code "175") (name "unconnected-(U7-PadPA8)") (class "Default")
      (node (ref "U7") (pin "PA8") (pinfunction "PA8_PA8") (pintype "bidirectional"))
    )
    (net (code "176") (name "unconnected-(U7-PadPA9)") (class "Default")
      (node (ref "U7") (pin "PA9") (pinfunction "PA9_PA9") (pintype "bidirectional"))
    )
    (net (code "177") (name "unconnected-(U7-PadPA10)") (class "Default")
      (node (ref "U7") (pin "PA10") (pinfunction "PA10_PA10") (pintype "bidirectional"))
    )
    (net (code "178") (name "unconnected-(U7-PadPA11)") (class "Default")
      (node (ref "U7") (pin "PA11") (pinfunction "PA11_PA11") (pintype "bidirectional"))
    )
    (net (code "179") (name "unconnected-(U7-PadPA12)") (class "Default")
      (node (ref "U7") (pin "PA12") (pinfunction "PA12_PA12") (pintype "bidirectional"))
    )
    (net (code "180") (name "unconnected-(U7-PadPA15)") (class "Default")
      (node (ref "U7") (pin "PA15") (pinfunction "PA15_PA15") (pintype "bidirectional"))
    )
    (net (code "181") (name "unconnected-(U7-PadPB1)") (class "Default")
      (node (ref "U7") (pin "PB1") (pinfunction "PB1_PB1") (pintype "bidirectional"))
    )
    (net (code "182") (name "unconnected-(U7-PadPB2)") (class "Default")
      (node (ref "U7") (pin "PB2") (pinfunction "PB2_PB2") (pintype "bidirectional"))
    )
    (net (code "183") (name "unconnected-(U7-PadPC6)") (class "Default")
      (node (ref "U7") (pin "PC6") (pinfunction "PC6_PC6") (pintype "bidirectional"))
    )
    (net (code "184") (name "unconnected-(U7-PadPC7)") (class "Default")
      (node (ref "U7") (pin "PC7") (pinfunction "PC7_PC7") (pintype "bidirectional"))
    )
    (net (code "185") (name "unconnected-(U7-PadPC8)") (class "Default")
      (node (ref "U7") (pin "PC8") (pinfunction "PC8_PC8") (pintype "bidirectional"))
    )
    (net (code "186") (name "unconnected-(U7-PadPC9)") (class "Default")
      (node (ref "U7") (pin "PC9") (pinfunction "PC9_PC9") (pintype "bidirectional"))
    )
    (net (code "187") (name "unconnected-(U7-PadPC10)") (class "Default")
      (node (ref "U7") (pin "PC10") (pinfunction "PC10_PC10") (pintype "bidirectional"))
    )
    (net (code "188") (name "unconnected-(U7-PadPC11)") (class "Default")
      (node (ref "U7") (pin "PC11") (pinfunction "PC11_PC11") (pintype "bidirectional"))
    )
    (net (code "189") (name "unconnected-(U7-PadPC12)") (class "Default")
      (node (ref "U7") (pin "PC12") (pinfunction "PC12_PC12") (pintype "bidirectional"))
    )
    (net (code "190") (name "unconnected-(U7-PadPC13)") (class "Default")
      (node (ref "U7") (pin "PC13") (pinfunction "PC13_PC13") (pintype "bidirectional"))
    )
    (net (code "191") (name "unconnected-(U7-PadPC14)") (class "Default")
      (node (ref "U7") (pin "PC14") (pinfunction "PC14_PC14") (pintype "bidirectional"))
    )
    (net (code "192") (name "unconnected-(U7-PadPC15)") (class "Default")
      (node (ref "U7") (pin "PC15") (pinfunction "PC15_PC15") (pintype "bidirectional"))
    )
    (net (code "193") (name "unconnected-(U7-PadPD2)") (class "Default")
      (node (ref "U7") (pin "PD2") (pinfunction "PD2_PD2") (pintype "bidirectional"))
    )
    (net (code "194") (name "unconnected-(U9-NC-PadNC1)") (class "Default")
      (node (ref "U9") (pin "NC1") (pinfunction "NC_NC1") (pintype "bidirectional"))
    )
    (net (code "195") (name "unconnected-(U9-NC-PadNC2)") (class "Default")
      (node (ref "U9") (pin "NC2") (pinfunction "NC_NC2") (pintype "bidirectional"))
    )
    (net (code "196") (name "unconnected-(U10-NC-PadNC1)") (class "Default")
      (node (ref "U10") (pin "NC1") (pinfunction "NC_NC1") (pintype "bidirectional"))
    )
    (net (code "197") (name "unconnected-(U10-NC-PadNC2)") (class "Default")
      (node (ref "U10") (pin "NC2") (pinfunction "NC_NC2") (pintype "bidirectional"))
    )
  )
)
